# Arch_GPRS_v2_0.net
KiCad netlist of a schematic drawn in EAGLE
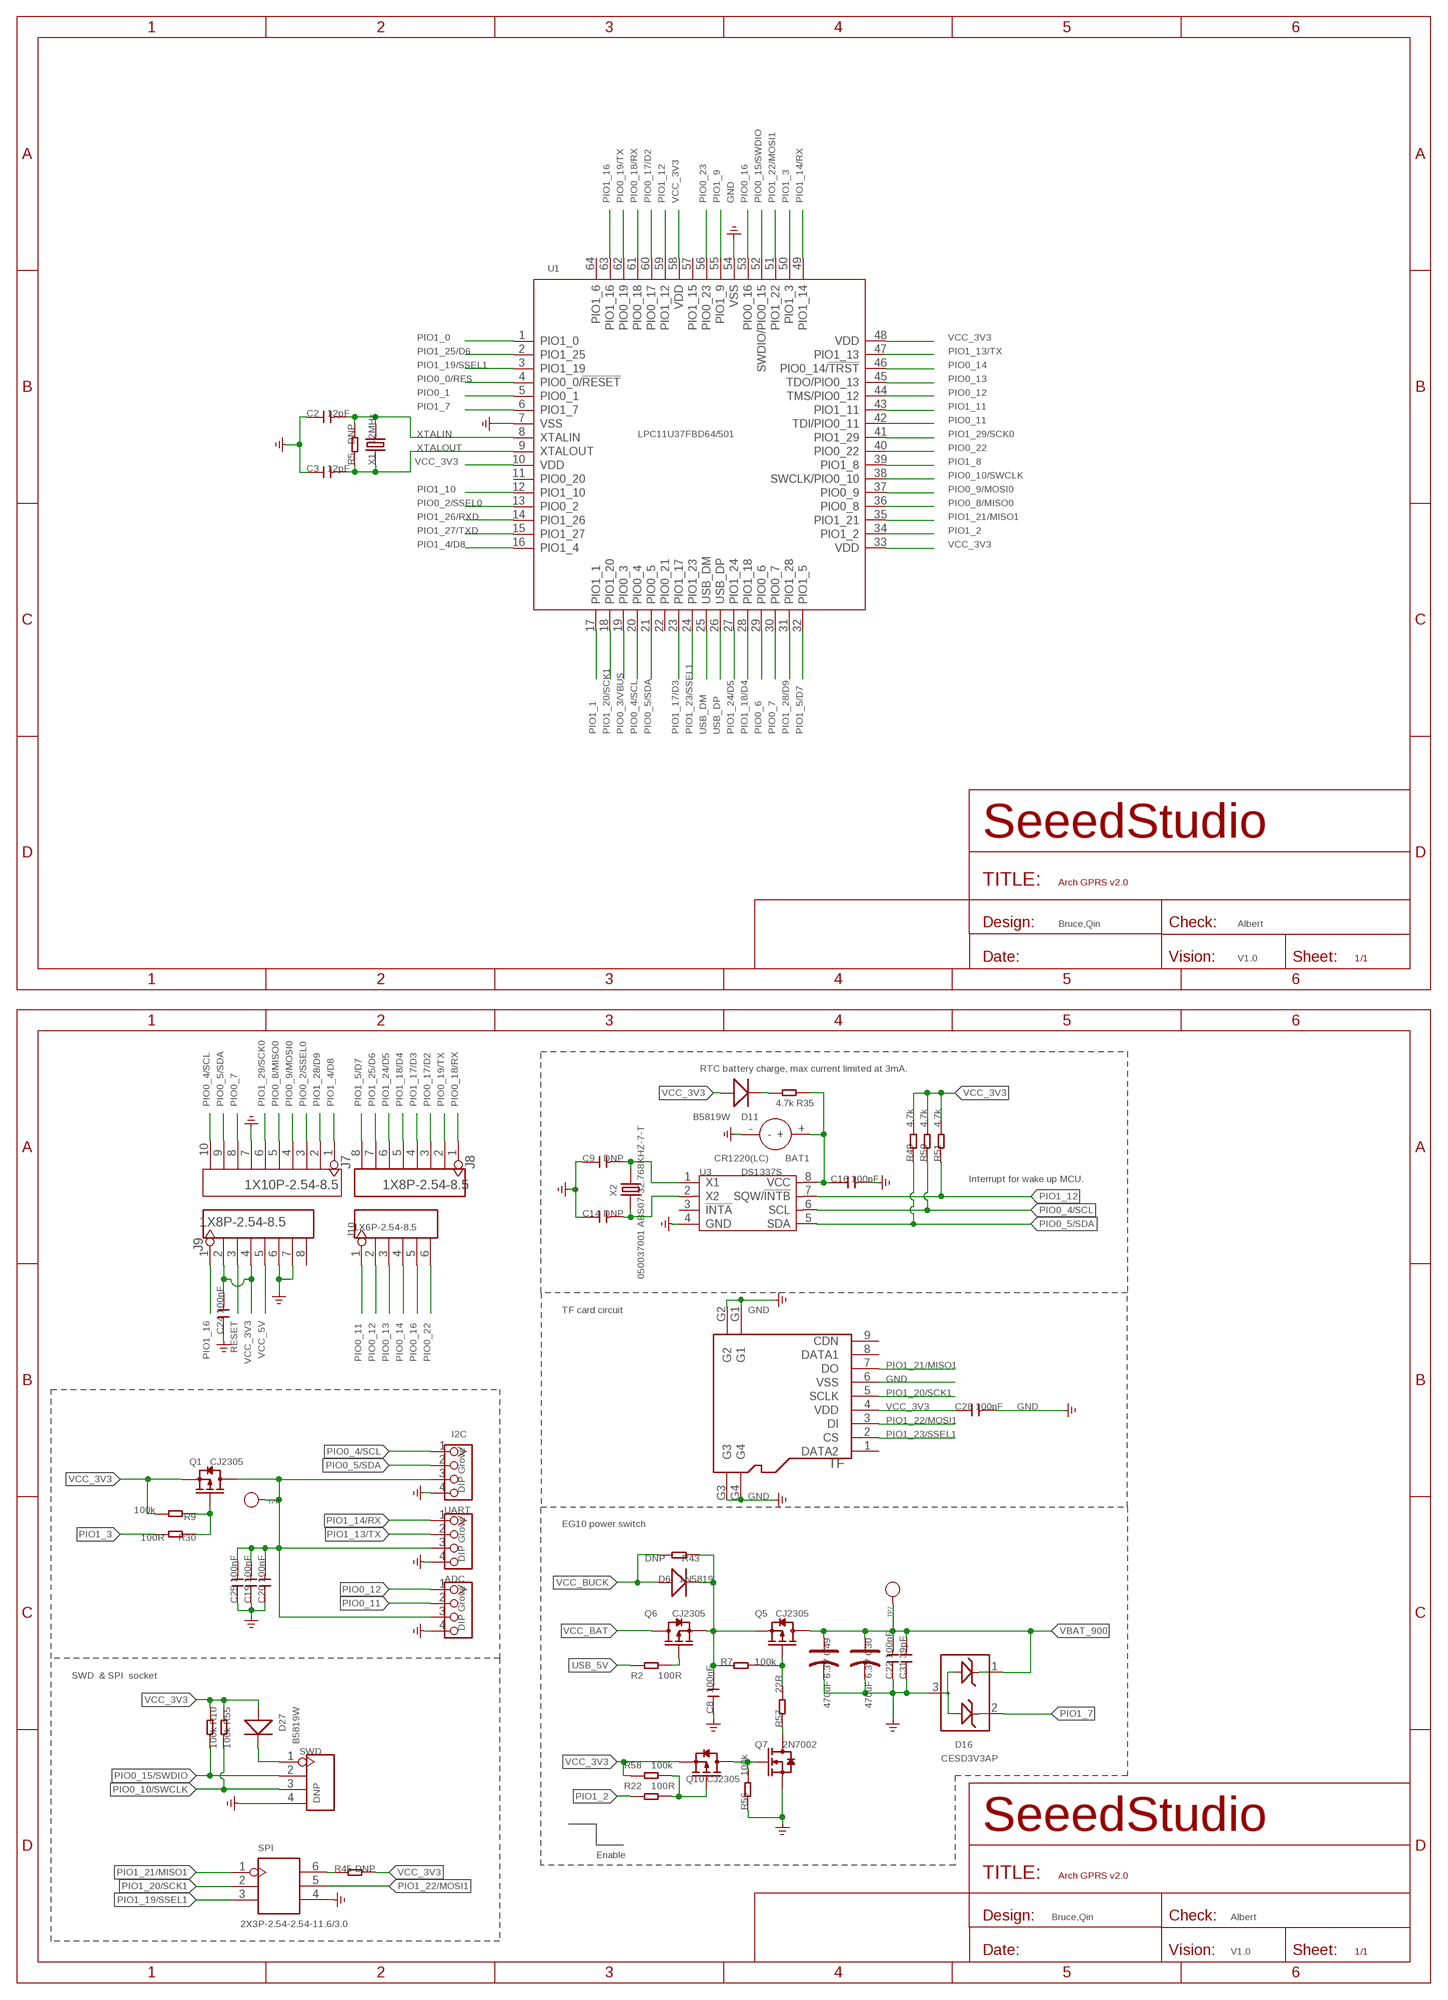
[diagram p0: schematic, sheet 1, part 1 of 2]
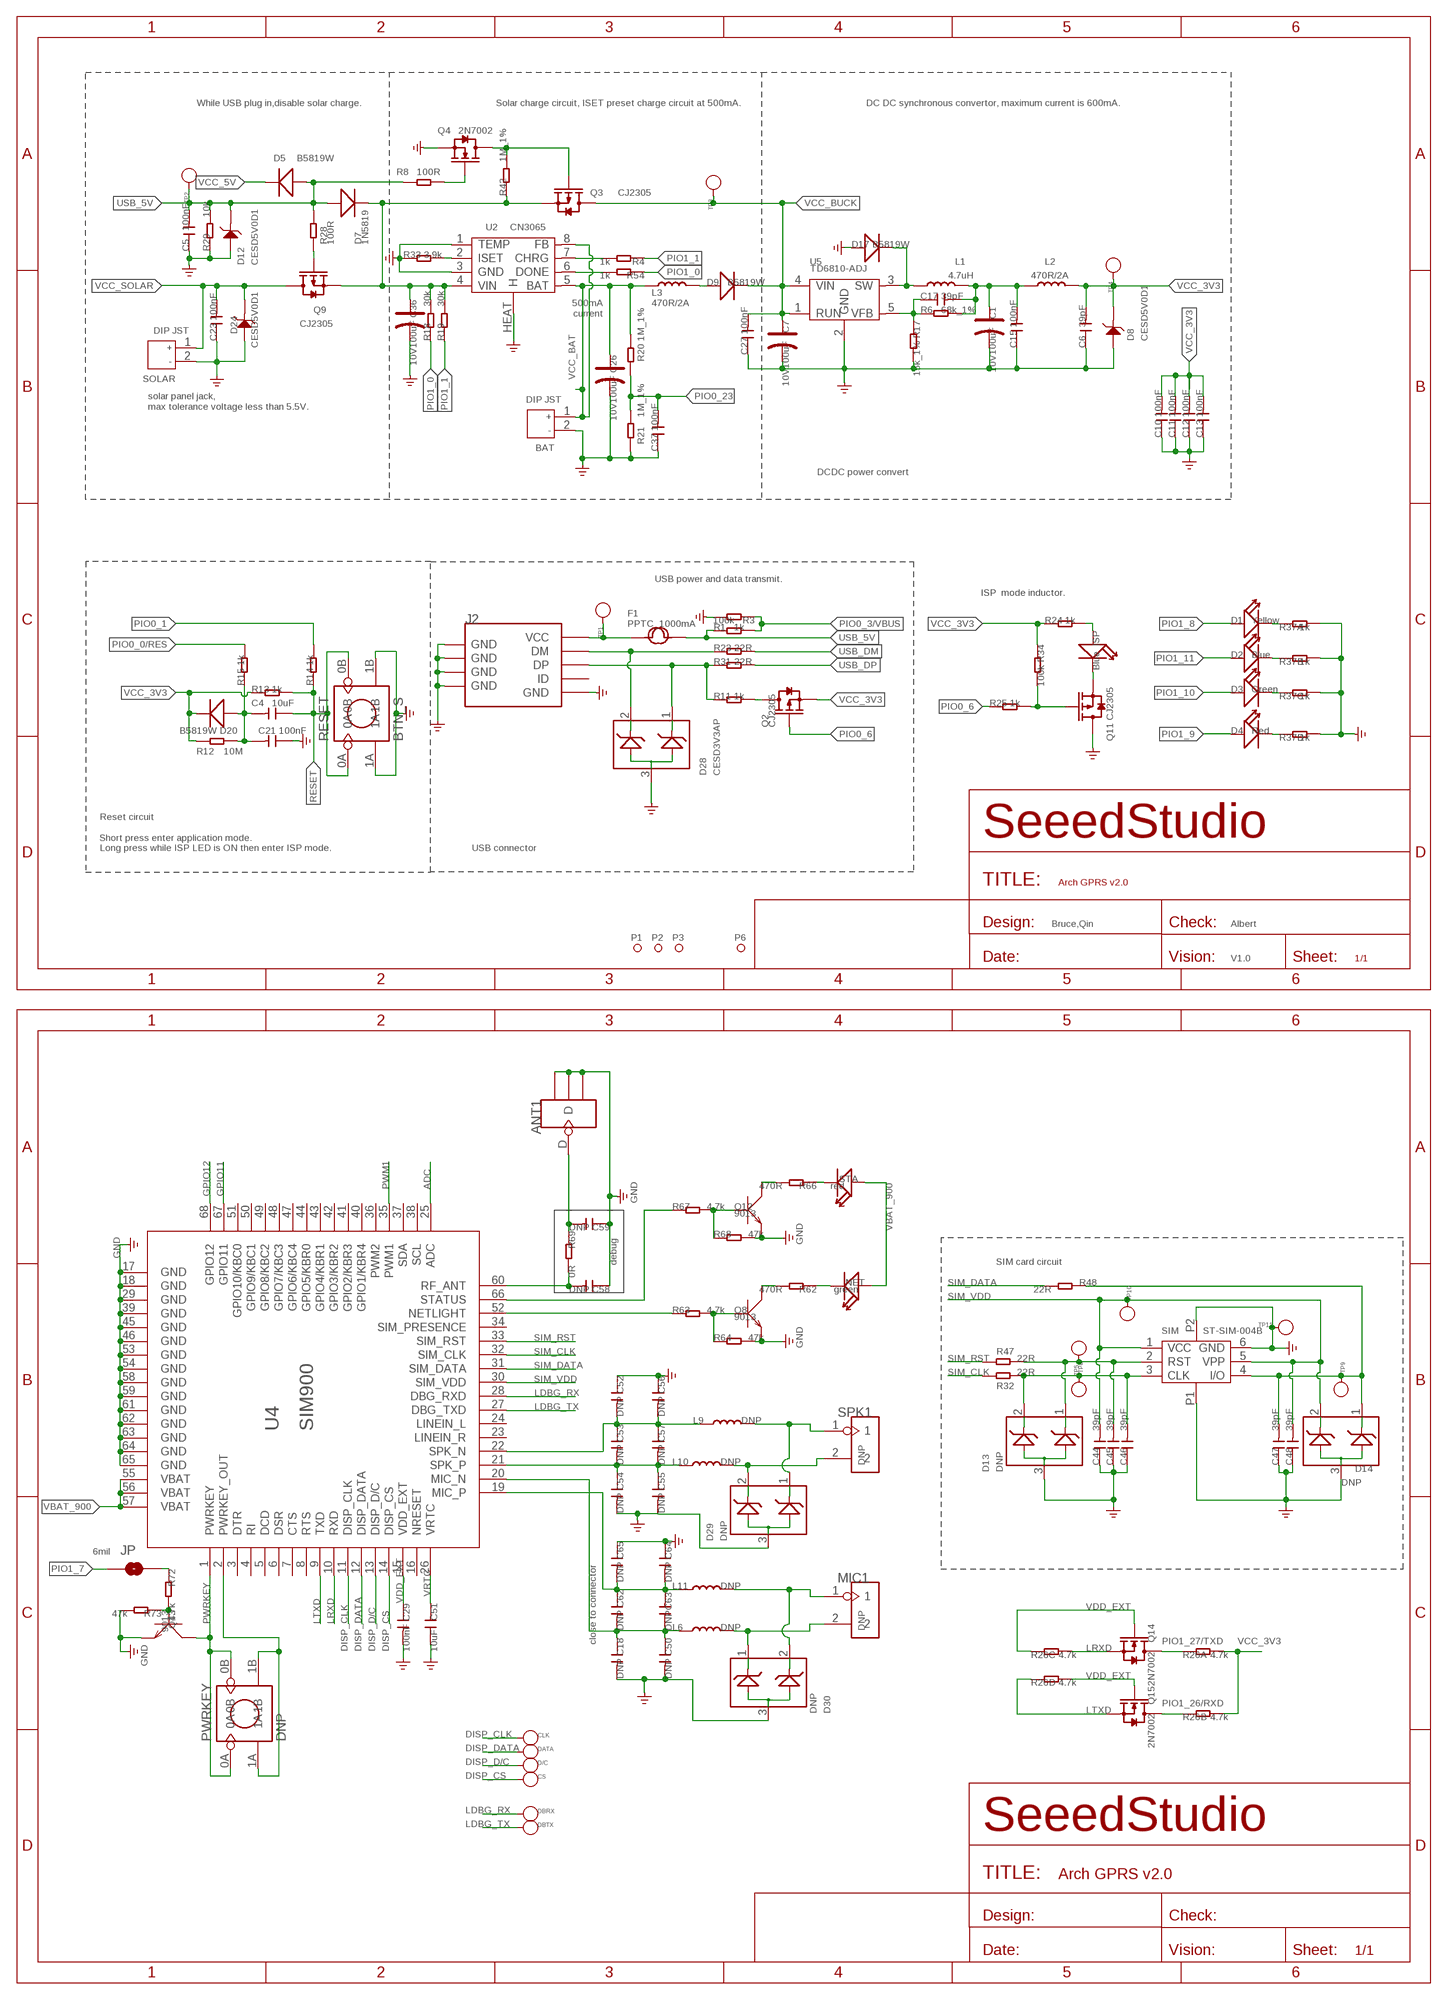
[diagram p1: schematic, sheet 1, part 2 of 2]

(export (version "E")
  (design (tool "Eeschema 10.0.6"))
  (components
    (comp (ref "ADC")
      (value "DIP Grove")
      (footprint "eagle-import:4P-2.0")
      (libsource (lib "eagle-import") (part "TWIG-4P-2.0-2.0"))
    )
    (comp (ref "ANT1")
      (value "ANTENNA-U-FL")
      (footprint "eagle-import:4P-U-FL")
      (libsource (lib "eagle-import") (part "ANTENNA-U-FL"))
    )
    (comp (ref "BAT")
      (value "DIP JST")
      (footprint "eagle-import:JST-2.0")
      (libsource (lib "eagle-import") (part "JACK-JST-2P-PW'2.0'"))
    )
    (comp (ref "BAT1")
      (value "CR1220(LC)")
      (footprint "eagle-import:2P-D12.55X2.22H")
      (libsource (lib "eagle-import") (part "BATTERY-3V"))
    )
    (comp (ref "C1")
      (value "10V100uF")
      (footprint "eagle-import:AVX-B")
      (libsource (lib "eagle-import") (part "CAP-AVX-B"))
    )
    (comp (ref "C2")
      (value "12pF")
      (footprint "eagle-import:C0603")
      (libsource (lib "eagle-import") (part "C-0603"))
    )
    (comp (ref "C3")
      (value "12pF")
      (footprint "eagle-import:C0603")
      (libsource (lib "eagle-import") (part "C-0603"))
    )
    (comp (ref "C4")
      (value "10uF")
      (footprint "eagle-import:C0805")
      (libsource (lib "eagle-import") (part "C-0805"))
    )
    (comp (ref "C5")
      (value "100nF")
      (footprint "eagle-import:C0603")
      (libsource (lib "eagle-import") (part "C-0603"))
    )
    (comp (ref "C6")
      (value "39pF")
      (footprint "eagle-import:C0603")
      (libsource (lib "eagle-import") (part "C-0603"))
    )
    (comp (ref "C7")
      (value "10V100uF")
      (footprint "eagle-import:AVX-B")
      (libsource (lib "eagle-import") (part "CAP-AVX-B"))
    )
    (comp (ref "C8")
      (value "100nF")
      (footprint "eagle-import:C0603")
      (libsource (lib "eagle-import") (part "C-0603"))
    )
    (comp (ref "C9")
      (value "DNP")
      (footprint "eagle-import:C0603")
      (libsource (lib "eagle-import") (part "C-0603"))
    )
    (comp (ref "C10")
      (value "100nF")
      (footprint "eagle-import:C0603")
      (libsource (lib "eagle-import") (part "C-0603"))
    )
    (comp (ref "C11")
      (value "100nF")
      (footprint "eagle-import:C0603")
      (libsource (lib "eagle-import") (part "C-0603"))
    )
    (comp (ref "C12")
      (value "100nF")
      (footprint "eagle-import:C0603")
      (libsource (lib "eagle-import") (part "C-0603"))
    )
    (comp (ref "C13")
      (value "100nF")
      (footprint "eagle-import:C0603")
      (libsource (lib "eagle-import") (part "C-0603"))
    )
    (comp (ref "C14")
      (value "DNP")
      (footprint "eagle-import:C0603")
      (libsource (lib "eagle-import") (part "C-0603"))
    )
    (comp (ref "C15")
      (value "100nF")
      (footprint "eagle-import:C0603")
      (libsource (lib "eagle-import") (part "C-0603"))
    )
    (comp (ref "C16")
      (value "100nF")
      (footprint "eagle-import:C0603")
      (libsource (lib "eagle-import") (part "C-0603"))
    )
    (comp (ref "C17")
      (value "39pF")
      (footprint "eagle-import:C0603")
      (libsource (lib "eagle-import") (part "C-0603"))
    )
    (comp (ref "C18")
      (value "DNP")
      (footprint "eagle-import:C0603")
      (libsource (lib "eagle-import") (part "C-0603"))
    )
    (comp (ref "C19")
      (value "100nF")
      (footprint "eagle-import:C0603")
      (libsource (lib "eagle-import") (part "C-0603"))
    )
    (comp (ref "C20")
      (value "100nF")
      (footprint "eagle-import:C0603")
      (libsource (lib "eagle-import") (part "C-0603"))
    )
    (comp (ref "C21")
      (value "100nF")
      (footprint "eagle-import:C0603")
      (libsource (lib "eagle-import") (part "C-0603"))
    )
    (comp (ref "C22")
      (value "100nF")
      (footprint "eagle-import:C0603")
      (libsource (lib "eagle-import") (part "C-0603"))
    )
    (comp (ref "C23")
      (value "100nF")
      (footprint "eagle-import:C0603")
      (libsource (lib "eagle-import") (part "C-0603"))
    )
    (comp (ref "C24")
      (value "100nF")
      (footprint "eagle-import:C0603")
      (libsource (lib "eagle-import") (part "C-0603"))
    )
    (comp (ref "C25")
      (value "100nF")
      (footprint "eagle-import:C0603")
      (libsource (lib "eagle-import") (part "C-0603"))
    )
    (comp (ref "C26")
      (value "10V100uF")
      (footprint "eagle-import:AVX-B")
      (libsource (lib "eagle-import") (part "CAP-AVX-B"))
    )
    (comp (ref "C27")
      (value "100nF")
      (footprint "eagle-import:C0603")
      (libsource (lib "eagle-import") (part "C-0603"))
    )
    (comp (ref "C28")
      (value "100nF")
      (footprint "eagle-import:C0603")
      (libsource (lib "eagle-import") (part "C-0603"))
    )
    (comp (ref "C29")
      (value "100nF")
      (footprint "eagle-import:C0603")
      (libsource (lib "eagle-import") (part "C-0603"))
    )
    (comp (ref "C30")
      (value "470uF 6.3V")
      (footprint "eagle-import:AVX-D")
      (libsource (lib "eagle-import") (part "CAP-AVX-D"))
    )
    (comp (ref "C31")
      (value "39pF")
      (footprint "eagle-import:C0603")
      (libsource (lib "eagle-import") (part "C-0603"))
    )
    (comp (ref "C36")
      (value "10V100uF")
      (footprint "eagle-import:AVX-B")
      (libsource (lib "eagle-import") (part "CAP-AVX-B"))
    )
    (comp (ref "C37")
      (value "100nF")
      (footprint "eagle-import:C0603")
      (libsource (lib "eagle-import") (part "C-0603"))
    )
    (comp (ref "C44")
      (value "39pF")
      (footprint "eagle-import:C0603")
      (libsource (lib "eagle-import") (part "C-0603"))
    )
    (comp (ref "C45")
      (value "39pF")
      (footprint "eagle-import:C0603")
      (libsource (lib "eagle-import") (part "C-0603"))
    )
    (comp (ref "C46")
      (value "39pF")
      (footprint "eagle-import:C0603")
      (libsource (lib "eagle-import") (part "C-0603"))
    )
    (comp (ref "C47")
      (value "39pF")
      (footprint "eagle-import:C0603")
      (libsource (lib "eagle-import") (part "C-0603"))
    )
    (comp (ref "C48")
      (value "39pF")
      (footprint "eagle-import:C0603")
      (libsource (lib "eagle-import") (part "C-0603"))
    )
    (comp (ref "C49")
      (value "470uF 6.3V")
      (footprint "eagle-import:AVX-D")
      (libsource (lib "eagle-import") (part "CAP-AVX-D"))
    )
    (comp (ref "C50")
      (value "DNP")
      (footprint "eagle-import:C0603")
      (libsource (lib "eagle-import") (part "C-0603"))
    )
    (comp (ref "C51")
      (value "10uF")
      (footprint "eagle-import:C0805")
      (libsource (lib "eagle-import") (part "C-0805"))
    )
    (comp (ref "C52")
      (value "DNP")
      (footprint "eagle-import:C0603")
      (libsource (lib "eagle-import") (part "C-0603"))
    )
    (comp (ref "C53")
      (value "DNP")
      (footprint "eagle-import:C0603")
      (libsource (lib "eagle-import") (part "C-0603"))
    )
    (comp (ref "C54")
      (value "DNP")
      (footprint "eagle-import:C0603")
      (libsource (lib "eagle-import") (part "C-0603"))
    )
    (comp (ref "C55")
      (value "DNP")
      (footprint "eagle-import:C0603")
      (libsource (lib "eagle-import") (part "C-0603"))
    )
    (comp (ref "C56")
      (value "DNP")
      (footprint "eagle-import:C0603")
      (libsource (lib "eagle-import") (part "C-0603"))
    )
    (comp (ref "C57")
      (value "DNP")
      (footprint "eagle-import:C0603")
      (libsource (lib "eagle-import") (part "C-0603"))
    )
    (comp (ref "C58")
      (value "DNP")
      (footprint "eagle-import:C0603")
      (libsource (lib "eagle-import") (part "C-0603"))
    )
    (comp (ref "C59")
      (value "DNP")
      (footprint "eagle-import:C0603")
      (libsource (lib "eagle-import") (part "C-0603"))
    )
    (comp (ref "C62")
      (value "DNP")
      (footprint "eagle-import:C0603")
      (libsource (lib "eagle-import") (part "C-0603"))
    )
    (comp (ref "C63")
      (value "DNP")
      (footprint "eagle-import:C0603")
      (libsource (lib "eagle-import") (part "C-0603"))
    )
    (comp (ref "C64")
      (value "DNP")
      (footprint "eagle-import:C0603")
      (libsource (lib "eagle-import") (part "C-0603"))
    )
    (comp (ref "C65")
      (value "DNP")
      (footprint "eagle-import:C0603")
      (libsource (lib "eagle-import") (part "C-0603"))
    )
    (comp (ref "CLK")
      (value "PAD-TEST-POINT-CIRCLE'4545'")
      (footprint "eagle-import:TP_4545")
      (fields (field (name "PARTNO") "DNP"))
      (libsource (lib "eagle-import") (part "PAD-TEST-POINT-CIRCLE'4545'"))
    )
    (comp (ref "CS")
      (value "PAD-TEST-POINT-CIRCLE'4545'")
      (footprint "eagle-import:TP_4545")
      (fields (field (name "PARTNO") "DNP"))
      (libsource (lib "eagle-import") (part "PAD-TEST-POINT-CIRCLE'4545'"))
    )
    (comp (ref "D/C")
      (value "PAD-TEST-POINT-CIRCLE'4545'")
      (footprint "eagle-import:TP_4545")
      (fields (field (name "PARTNO") "DNP"))
      (libsource (lib "eagle-import") (part "PAD-TEST-POINT-CIRCLE'4545'"))
    )
    (comp (ref "D1")
      (value "Yellow")
      (footprint "eagle-import:LED-0603")
      (libsource (lib "eagle-import") (part "LED'0603'"))
    )
    (comp (ref "D2")
      (value "Blue")
      (footprint "eagle-import:LED-0603")
      (libsource (lib "eagle-import") (part "LED'0603'"))
    )
    (comp (ref "D3")
      (value "Green")
      (footprint "eagle-import:LED-0603")
      (libsource (lib "eagle-import") (part "LED'0603'"))
    )
    (comp (ref "D4")
      (value "Red")
      (footprint "eagle-import:LED-0603")
      (libsource (lib "eagle-import") (part "LED'0603'"))
    )
    (comp (ref "D5")
      (value "B5819W")
      (footprint "eagle-import:SOD123")
      (libsource (lib "eagle-import") (part "D'1206'"))
    )
    (comp (ref "D6")
      (value "1N5819")
      (footprint "eagle-import:SMA")
      (libsource (lib "eagle-import") (part "D'B130L-13-F'"))
    )
    (comp (ref "D7")
      (value "1N5819")
      (footprint "eagle-import:SMA")
      (libsource (lib "eagle-import") (part "D'B130L-13-F'"))
    )
    (comp (ref "D8")
      (value "CESD5V0D1")
      (footprint "eagle-import:SOD123-2.7X1.6")
      (libsource (lib "eagle-import") (part "D-ESD-2P'CESD5V0D1'"))
    )
    (comp (ref "D9")
      (value "B5819W")
      (footprint "eagle-import:SOD123")
      (libsource (lib "eagle-import") (part "D'1206'"))
    )
    (comp (ref "D11")
      (value "B5819W")
      (footprint "eagle-import:SOD123")
      (libsource (lib "eagle-import") (part "D'1206'"))
    )
    (comp (ref "D12")
      (value "CESD5V0D1")
      (footprint "eagle-import:SOD123-2.7X1.6")
      (libsource (lib "eagle-import") (part "D-ESD-2P'CESD5V0D1'"))
    )
    (comp (ref "D13")
      (value "DNP")
      (footprint "eagle-import:SOT23")
      (libsource (lib "eagle-import") (part "D-ESD-3P"))
    )
    (comp (ref "D14")
      (value "DNP")
      (footprint "eagle-import:SOT23")
      (libsource (lib "eagle-import") (part "D-ESD-3P"))
    )
    (comp (ref "D16")
      (value "CESD3V3AP")
      (footprint "eagle-import:SOT23")
      (libsource (lib "eagle-import") (part "D-ESD-3P"))
    )
    (comp (ref "D17")
      (value "B5819W")
      (footprint "eagle-import:SOD123")
      (libsource (lib "eagle-import") (part "D'1206'"))
    )
    (comp (ref "D20")
      (value "B5819W")
      (footprint "eagle-import:SOD123")
      (libsource (lib "eagle-import") (part "D'1206'"))
    )
    (comp (ref "D24")
      (value "CESD5V0D1")
      (footprint "eagle-import:SOD123-2.7X1.6")
      (libsource (lib "eagle-import") (part "D-ESD-2P'CESD5V0D1'"))
    )
    (comp (ref "D27")
      (value "B5819W")
      (footprint "eagle-import:SOD123")
      (libsource (lib "eagle-import") (part "D'1206'"))
    )
    (comp (ref "D28")
      (value "CESD3V3AP")
      (footprint "eagle-import:SOT23")
      (libsource (lib "eagle-import") (part "D-ESD-3P"))
    )
    (comp (ref "D29")
      (value "DNP")
      (footprint "eagle-import:SOT23")
      (libsource (lib "eagle-import") (part "D-ESD-3P"))
    )
    (comp (ref "D30")
      (value "DNP")
      (footprint "eagle-import:SOT23")
      (libsource (lib "eagle-import") (part "D-ESD-3P"))
    )
    (comp (ref "DATA")
      (value "PAD-TEST-POINT-CIRCLE'4545'")
      (footprint "eagle-import:TP_4545")
      (fields (field (name "PARTNO") "DNP"))
      (libsource (lib "eagle-import") (part "PAD-TEST-POINT-CIRCLE'4545'"))
    )
    (comp (ref "DBRX")
      (value "DBURX")
      (footprint "eagle-import:TP_4545")
      (fields (field (name "PARTNO") "DNP"))
      (libsource (lib "eagle-import") (part "PAD-TEST-POINT-CIRCLE'4545'"))
    )
    (comp (ref "DBTX")
      (value "PAD-TEST-POINT-CIRCLE'4545'")
      (footprint "eagle-import:TP_4545")
      (fields (field (name "PARTNO") "DNP"))
      (libsource (lib "eagle-import") (part "PAD-TEST-POINT-CIRCLE'4545'"))
    )
    (comp (ref "F1")
      (value "PPTC_1000mA")
      (footprint "eagle-import:F1206")
      (libsource (lib "eagle-import") (part "FUSE'1206'"))
    )
    (comp (ref "I2C")
      (value "DIP Grove")
      (footprint "eagle-import:4P-2.0")
      (libsource (lib "eagle-import") (part "TWIG-4P-2.0-2.0"))
    )
    (comp (ref "ISP")
      (value "Blue")
      (footprint "eagle-import:LED-0603")
      (libsource (lib "eagle-import") (part "LED'0603'"))
    )
    (comp (ref "J2")
      (value "USB-MINIUSB-5P-MICRO")
      (footprint "eagle-import:MICRO-USB")
      (libsource (lib "eagle-import") (part "USB-MINIUSB-5P-MICRO"))
    )
    (comp (ref "J7")
      (value "1X10P-2.54-8.5")
      (footprint "eagle-import:10P-2.54")
      (libsource (lib "eagle-import") (part "HEADER-10P-2.54"))
    )
    (comp (ref "J8")
      (value "1X8P-2.54-8.5")
      (footprint "eagle-import:8P-2.54")
      (libsource (lib "eagle-import") (part "HEADER-8P-2.54"))
    )
    (comp (ref "J9")
      (value "1X8P-2.54-8.5")
      (footprint "eagle-import:8P-2.54")
      (libsource (lib "eagle-import") (part "HEADER-8P-2.54"))
    )
    (comp (ref "J10")
      (value "1X6P-2.54-8.5")
      (footprint "eagle-import:6P-2.54-65_35MIL")
      (libsource (lib "eagle-import") (part "HEADER-6P-65/35MIL"))
    )
    (comp (ref "JP")
      (value "PAD-SOLDERJUMPERNC")
      (footprint "eagle-import:2P-SMD-3.3X2")
      (libsource (lib "eagle-import") (part "PAD-SOLDERJUMPERNC"))
    )
    (comp (ref "L1")
      (value "4.7uH")
      (footprint "eagle-import:L0420")
      (libsource (lib "eagle-import") (part "LSPD3D16-4R7M"))
    )
    (comp (ref "L2")
      (value "470R/2A")
      (footprint "eagle-import:L0805")
      (libsource (lib "eagle-import") (part "L'0805'"))
    )
    (comp (ref "L3")
      (value "470R/2A")
      (footprint "eagle-import:L0805")
      (libsource (lib "eagle-import") (part "L'0805'"))
    )
    (comp (ref "L6")
      (value "DNP")
      (footprint "eagle-import:L0603")
      (libsource (lib "eagle-import") (part "L'0603'"))
    )
    (comp (ref "L9")
      (value "DNP")
      (footprint "eagle-import:L0603")
      (libsource (lib "eagle-import") (part "L'0603'"))
    )
    (comp (ref "L10")
      (value "DNP")
      (footprint "eagle-import:L0603")
      (libsource (lib "eagle-import") (part "L'0603'"))
    )
    (comp (ref "L11")
      (value "DNP")
      (footprint "eagle-import:L0603")
      (libsource (lib "eagle-import") (part "L'0603'"))
    )
    (comp (ref "MIC1")
      (value "DNP")
      (footprint "eagle-import:2P-2.0")
      (libsource (lib "eagle-import") (part "HEADER-2P-2.0"))
    )
    (comp (ref "NET")
      (value "green")
      (footprint "eagle-import:LED-0603")
      (libsource (lib "eagle-import") (part "LED'0603'"))
    )
    (comp (ref "P1")
      (value "PAD-MARK")
      (footprint "eagle-import:ROUND-MARK-1.0")
      (fields (field (name "PARTNO") "DNP"))
      (libsource (lib "eagle-import") (part "PAD-MARK"))
    )
    (comp (ref "P2")
      (value "PAD-MARK")
      (footprint "eagle-import:ROUND-MARK-1.0")
      (fields (field (name "PARTNO") "DNP"))
      (libsource (lib "eagle-import") (part "PAD-MARK"))
    )
    (comp (ref "P3")
      (value "PAD-MARK")
      (footprint "eagle-import:ROUND-MARK-1.0")
      (fields (field (name "PARTNO") "DNP"))
      (libsource (lib "eagle-import") (part "PAD-MARK"))
    )
    (comp (ref "P6")
      (value "PAD-MARK")
      (footprint "eagle-import:ROUND-MARK-1.0")
      (fields (field (name "PARTNO") "DNP"))
      (libsource (lib "eagle-import") (part "PAD-MARK"))
    )
    (comp (ref "PWRKEY")
      (value "DNP")
      (footprint "eagle-import:BTN_S")
      (libsource (lib "eagle-import") (part "BTN_S"))
    )
    (comp (ref "Q1")
      (value "CJ2305")
      (footprint "eagle-import:SOT23")
      (libsource (lib "eagle-import") (part "MOSFET-P'SI2323CDS/SI2305DS{lt}BR{gt}'"))
    )
    (comp (ref "Q2")
      (value "CJ2305")
      (footprint "eagle-import:SOT23")
      (libsource (lib "eagle-import") (part "MOSFET-P'SI2323CDS/SI2305DS{lt}BR{gt}'"))
    )
    (comp (ref "Q3")
      (value "CJ2305")
      (footprint "eagle-import:SOT23")
      (libsource (lib "eagle-import") (part "MOSFET-P'SI2323CDS/SI2305DS{lt}BR{gt}'"))
    )
    (comp (ref "Q4")
      (value "2N7002")
      (footprint "eagle-import:SOT23")
      (libsource (lib "eagle-import") (part "MOSFET-N'SOT23'"))
    )
    (comp (ref "Q5")
      (value "CJ2305")
      (footprint "eagle-import:SOT23")
      (libsource (lib "eagle-import") (part "MOSFET-P'SI2323CDS/SI2305DS{lt}BR{gt}'"))
    )
    (comp (ref "Q6")
      (value "CJ2305")
      (footprint "eagle-import:SOT23")
      (libsource (lib "eagle-import") (part "MOSFET-P'SI2323CDS/SI2305DS{lt}BR{gt}'"))
    )
    (comp (ref "Q7")
      (value "2N7002")
      (footprint "eagle-import:SOT23")
      (libsource (lib "eagle-import") (part "MOSFET-N'SOT23'"))
    )
    (comp (ref "Q8")
      (value "9013")
      (footprint "eagle-import:SOT23")
      (libsource (lib "eagle-import") (part "TRANSISTOR-NPN-SOT23"))
    )
    (comp (ref "Q9")
      (value "CJ2305")
      (footprint "eagle-import:SOT23")
      (libsource (lib "eagle-import") (part "MOSFET-P'SI2323CDS/SI2305DS{lt}BR{gt}'"))
    )
    (comp (ref "Q10")
      (value "CJ2305")
      (footprint "eagle-import:SOT23")
      (libsource (lib "eagle-import") (part "MOSFET-P'SI2323CDS/SI2305DS{lt}BR{gt}'"))
    )
    (comp (ref "Q11")
      (value "CJ2305")
      (footprint "eagle-import:SOT23")
      (libsource (lib "eagle-import") (part "MOSFET-P'SI2323CDS/SI2305DS{lt}BR{gt}'"))
    )
    (comp (ref "Q12")
      (value "9013")
      (footprint "eagle-import:SOT23")
      (libsource (lib "eagle-import") (part "TRANSISTOR-NPN-SOT23"))
    )
    (comp (ref "Q13")
      (value "9013")
      (footprint "eagle-import:SOT23")
      (libsource (lib "eagle-import") (part "TRANSISTOR-NPN-SOT23"))
    )
    (comp (ref "Q14")
      (value "2N7002")
      (footprint "eagle-import:SOT23")
      (libsource (lib "eagle-import") (part "MOSFET-N'SOT23'"))
    )
    (comp (ref "Q15")
      (value "2N7002")
      (footprint "eagle-import:SOT23")
      (libsource (lib "eagle-import") (part "MOSFET-N'SOT23'"))
    )
    (comp (ref "R1")
      (value "1k")
      (footprint "eagle-import:R0603")
      (libsource (lib "eagle-import") (part "R-0603"))
    )
    (comp (ref "R2")
      (value "100R")
      (footprint "eagle-import:R0603")
      (libsource (lib "eagle-import") (part "R-0603"))
    )
    (comp (ref "R3")
      (value "100k")
      (footprint "eagle-import:R0603")
      (libsource (lib "eagle-import") (part "R-0603"))
    )
    (comp (ref "R4")
      (value "1k")
      (footprint "eagle-import:R0603")
      (libsource (lib "eagle-import") (part "R-0603"))
    )
    (comp (ref "R5")
      (value "DNP")
      (footprint "eagle-import:R0603")
      (libsource (lib "eagle-import") (part "R-0603"))
    )
    (comp (ref "R6")
      (value "68k_1%")
      (footprint "eagle-import:R0603")
      (libsource (lib "eagle-import") (part "R-0603"))
    )
    (comp (ref "R7")
      (value "100k")
      (footprint "eagle-import:R0603")
      (libsource (lib "eagle-import") (part "R-0603"))
    )
    (comp (ref "R8")
      (value "100R")
      (footprint "eagle-import:R0603")
      (libsource (lib "eagle-import") (part "R-0603"))
    )
    (comp (ref "R9")
      (value "100k")
      (footprint "eagle-import:R0603")
      (libsource (lib "eagle-import") (part "R-0603"))
    )
    (comp (ref "R10")
      (value "100k")
      (footprint "eagle-import:R0603")
      (libsource (lib "eagle-import") (part "R-0603"))
    )
    (comp (ref "R11")
      (value "1k")
      (footprint "eagle-import:R0603")
      (libsource (lib "eagle-import") (part "R-0603"))
    )
    (comp (ref "R12")
      (value "10M")
      (footprint "eagle-import:R0603")
      (libsource (lib "eagle-import") (part "R-0603"))
    )
    (comp (ref "R13")
      (value "1k")
      (footprint "eagle-import:R0603")
      (libsource (lib "eagle-import") (part "R-0603"))
    )
    (comp (ref "R14")
      (value "1k")
      (footprint "eagle-import:R0603")
      (libsource (lib "eagle-import") (part "R-0603"))
    )
    (comp (ref "R15")
      (value "1k")
      (footprint "eagle-import:R0603")
      (libsource (lib "eagle-import") (part "R-0603"))
    )
    (comp (ref "R17")
      (value "15k_1%")
      (footprint "eagle-import:R0603")
      (libsource (lib "eagle-import") (part "R-0603"))
    )
    (comp (ref "R18")
      (value "30k")
      (footprint "eagle-import:R0603")
      (libsource (lib "eagle-import") (part "R-0603"))
    )
    (comp (ref "R19")
      (value "30k")
      (footprint "eagle-import:R0603")
      (libsource (lib "eagle-import") (part "R-0603"))
    )
    (comp (ref "R20")
      (value "1M_1%")
      (footprint "eagle-import:R0603")
      (libsource (lib "eagle-import") (part "R-0603"))
    )
    (comp (ref "R21")
      (value "1M_1%")
      (footprint "eagle-import:R0603")
      (libsource (lib "eagle-import") (part "R-0603"))
    )
    (comp (ref "R22")
      (value "100R")
      (footprint "eagle-import:R0603")
      (libsource (lib "eagle-import") (part "R-0603"))
    )
    (comp (ref "R23")
      (value "22R")
      (footprint "eagle-import:R0603")
      (libsource (lib "eagle-import") (part "R-0603"))
    )
    (comp (ref "R24")
      (value "1k")
      (footprint "eagle-import:R0603")
      (libsource (lib "eagle-import") (part "R-0603"))
    )
    (comp (ref "R25")
      (value "1k")
      (footprint "eagle-import:R0603")
      (libsource (lib "eagle-import") (part "R-0603"))
    )
    (comp (ref "R26")
      (value "4.7k")
      (footprint "eagle-import:1206-8-3.3X2.4")
      (libsource (lib "eagle-import") (part "R-4R-1206"))
    )
    (comp (ref "R28")
      (value "100R")
      (footprint "eagle-import:R0603")
      (libsource (lib "eagle-import") (part "R-0603"))
    )
    (comp (ref "R29")
      (value "10k")
      (footprint "eagle-import:R0603")
      (libsource (lib "eagle-import") (part "R-0603"))
    )
    (comp (ref "R30")
      (value "100R")
      (footprint "eagle-import:R0603")
      (libsource (lib "eagle-import") (part "R-0603"))
    )
    (comp (ref "R31")
      (value "22R")
      (footprint "eagle-import:R0603")
      (libsource (lib "eagle-import") (part "R-0603"))
    )
    (comp (ref "R32")
      (value "22R")
      (footprint "eagle-import:R0603")
      (libsource (lib "eagle-import") (part "R-0603"))
    )
    (comp (ref "R33")
      (value "3.9k")
      (footprint "eagle-import:R0603")
      (libsource (lib "eagle-import") (part "R-0603"))
    )
    (comp (ref "R34")
      (value "100k")
      (footprint "eagle-import:R0603")
      (libsource (lib "eagle-import") (part "R-0603"))
    )
    (comp (ref "R35")
      (value "4.7k")
      (footprint "eagle-import:R0603")
      (libsource (lib "eagle-import") (part "R-0603"))
    )
    (comp (ref "R37")
      (value "1k")
      (footprint "eagle-import:1206-8-3.3X2.4")
      (libsource (lib "eagle-import") (part "R-4R-1206"))
    )
    (comp (ref "R42")
      (value "1M_1%")
      (footprint "eagle-import:R0603")
      (libsource (lib "eagle-import") (part "R-0603"))
    )
    (comp (ref "R43")
      (value "DNP")
      (footprint "eagle-import:R0603")
      (libsource (lib "eagle-import") (part "R-0603"))
    )
    (comp (ref "R45")
      (value "DNP")
      (footprint "eagle-import:R0603")
      (libsource (lib "eagle-import") (part "R-0603"))
    )
    (comp (ref "R47")
      (value "22R")
      (footprint "eagle-import:R0603")
      (libsource (lib "eagle-import") (part "R-0603"))
    )
    (comp (ref "R48")
      (value "22R")
      (footprint "eagle-import:R0603")
      (libsource (lib "eagle-import") (part "R-0603"))
    )
    (comp (ref "R49")
      (value "4.7k")
      (footprint "eagle-import:R0603")
      (libsource (lib "eagle-import") (part "R-0603"))
    )
    (comp (ref "R50")
      (value "4.7k")
      (footprint "eagle-import:R0603")
      (libsource (lib "eagle-import") (part "R-0603"))
    )
    (comp (ref "R51")
      (value "4.7k")
      (footprint "eagle-import:R0603")
      (libsource (lib "eagle-import") (part "R-0603"))
    )
    (comp (ref "R54")
      (value "1k")
      (footprint "eagle-import:R0603")
      (libsource (lib "eagle-import") (part "R-0603"))
    )
    (comp (ref "R55")
      (value "100k")
      (footprint "eagle-import:R0603")
      (libsource (lib "eagle-import") (part "R-0603"))
    )
    (comp (ref "R56")
      (value "100k")
      (footprint "eagle-import:R0603")
      (libsource (lib "eagle-import") (part "R-0603"))
    )
    (comp (ref "R57")
      (value "22R")
      (footprint "eagle-import:R0603")
      (libsource (lib "eagle-import") (part "R-0603"))
    )
    (comp (ref "R58")
      (value "100k")
      (footprint "eagle-import:R0603")
      (libsource (lib "eagle-import") (part "R-0603"))
    )
    (comp (ref "R62")
      (value "470R")
      (footprint "eagle-import:R0603")
      (libsource (lib "eagle-import") (part "R-0603"))
    )
    (comp (ref "R63")
      (value "4.7k")
      (footprint "eagle-import:R0603")
      (libsource (lib "eagle-import") (part "R-0603"))
    )
    (comp (ref "R64")
      (value "47k")
      (footprint "eagle-import:R0603")
      (libsource (lib "eagle-import") (part "R-0603"))
    )
    (comp (ref "R66")
      (value "470R")
      (footprint "eagle-import:R0603")
      (libsource (lib "eagle-import") (part "R-0603"))
    )
    (comp (ref "R67")
      (value "4.7k")
      (footprint "eagle-import:R0603")
      (libsource (lib "eagle-import") (part "R-0603"))
    )
    (comp (ref "R68")
      (value "47k")
      (footprint "eagle-import:R0603")
      (libsource (lib "eagle-import") (part "R-0603"))
    )
    (comp (ref "R69")
      (value "0R")
      (footprint "eagle-import:R0603")
      (libsource (lib "eagle-import") (part "R-0603"))
    )
    (comp (ref "R72")
      (value "4.7k")
      (footprint "eagle-import:R0603")
      (libsource (lib "eagle-import") (part "R-0603"))
    )
    (comp (ref "R73")
      (value "47k")
      (footprint "eagle-import:R0603")
      (libsource (lib "eagle-import") (part "R-0603"))
    )
    (comp (ref "RESET")
      (value "BTN_S")
      (footprint "eagle-import:BTN_S")
      (libsource (lib "eagle-import") (part "BTN_S"))
    )
    (comp (ref "SIM")
      (value "ST-SIM-004B")
      (footprint "eagle-import:6P-1.8")
      (libsource (lib "eagle-import") (part "SIM-CARD'ST-SIM-004B'"))
    )
    (comp (ref "SOLAR")
      (value "DIP JST")
      (footprint "eagle-import:JST-2.0")
      (libsource (lib "eagle-import") (part "JACK-JST-2P-PW'2.0'"))
    )
    (comp (ref "SPI")
      (value "2X3P-2.54-2.54-11.6/3.0")
      (footprint "eagle-import:2X3P-2.54")
      (libsource (lib "eagle-import") (part "HEADER-2X3P-2.54"))
    )
    (comp (ref "SPK1")
      (value "DNP")
      (footprint "eagle-import:2P-2.0")
      (libsource (lib "eagle-import") (part "HEADER-2P-2.0"))
    )
    (comp (ref "STA")
      (value "red")
      (footprint "eagle-import:LED-0603")
      (libsource (lib "eagle-import") (part "LED'0603'"))
    )
    (comp (ref "SWD")
      (value "DNP")
      (footprint "eagle-import:4P-65_35MIL")
      (libsource (lib "eagle-import") (part "HEADER-4P-65/35MIL"))
    )
    (comp (ref "TF")
      (value "HOLDER-MICROSD-9P'HOLDER'")
      (footprint "eagle-import:9P-SMD-W_-RING")
      (libsource (lib "eagle-import") (part "HOLDER-MICROSD-9P'HOLDER'"))
    )
    (comp (ref "TP1")
      (value "PAD-TEST-POINT'4545'")
      (footprint "eagle-import:TP_4545")
      (fields (field (name "PARTNO") "DNP"))
      (libsource (lib "eagle-import") (part "PAD-TEST-POINT'4545'"))
    )
    (comp (ref "TP2")
      (value "PAD-TEST-POINT'4545'")
      (footprint "eagle-import:TP_4545")
      (fields (field (name "PARTNO") "DNP"))
      (libsource (lib "eagle-import") (part "PAD-TEST-POINT'4545'"))
    )
    (comp (ref "TP3")
      (value "PAD-TEST-POINT'4545'")
      (footprint "eagle-import:TP_4545")
      (fields (field (name "PARTNO") "DNP"))
      (libsource (lib "eagle-import") (part "PAD-TEST-POINT'4545'"))
    )
    (comp (ref "TP4")
      (value "PAD-TEST-POINT'4545'")
      (footprint "eagle-import:TP_4545")
      (fields (field (name "PARTNO") "DNP"))
      (libsource (lib "eagle-import") (part "PAD-TEST-POINT'4545'"))
    )
    (comp (ref "TP5")
      (value "PAD-TEST-POINT'4545'")
      (footprint "eagle-import:TP_4545")
      (fields (field (name "PARTNO") "DNP"))
      (libsource (lib "eagle-import") (part "PAD-TEST-POINT'4545'"))
    )
    (comp (ref "TP6")
      (value "PAD-TEST-POINT'4545'")
      (footprint "eagle-import:TP_4545")
      (fields (field (name "PARTNO") "DNP"))
      (libsource (lib "eagle-import") (part "PAD-TEST-POINT'4545'"))
    )
    (comp (ref "TP7")
      (value "PAD-TEST-POINT'4545'")
      (footprint "eagle-import:TP_4545")
      (fields (field (name "PARTNO") "DNP"))
      (libsource (lib "eagle-import") (part "PAD-TEST-POINT'4545'"))
    )
    (comp (ref "TP8")
      (value "PAD-TEST-POINT'4545'")
      (footprint "eagle-import:TP_4545")
      (fields (field (name "PARTNO") "DNP"))
      (libsource (lib "eagle-import") (part "PAD-TEST-POINT'4545'"))
    )
    (comp (ref "TP9")
      (value "PAD-TEST-POINT'4545'")
      (footprint "eagle-import:TP_4545")
      (fields (field (name "PARTNO") "DNP"))
      (libsource (lib "eagle-import") (part "PAD-TEST-POINT'4545'"))
    )
    (comp (ref "TP10")
      (value "PAD-TEST-POINT'4545'")
      (footprint "eagle-import:TP_4545")
      (fields (field (name "PARTNO") "DNP"))
      (libsource (lib "eagle-import") (part "PAD-TEST-POINT'4545'"))
    )
    (comp (ref "TP11")
      (value "PAD-TEST-POINT'4545'")
      (footprint "eagle-import:TP_4545")
      (fields (field (name "PARTNO") "DNP"))
      (libsource (lib "eagle-import") (part "PAD-TEST-POINT'4545'"))
    )
    (comp (ref "U1")
      (value "LPC11U37FBD64/501")
      (footprint "eagle-import:LQFP64")
      (libsource (lib "eagle-import") (part "LPC11U37FBD64/501"))
    )
    (comp (ref "U2")
      (value "CN3065")
      (footprint "eagle-import:DFN8")
      (libsource (lib "eagle-import") (part "CN3065-DFN8"))
    )
    (comp (ref "U3")
      (value "DS1337S")
      (footprint "eagle-import:SOP8")
      (libsource (lib "eagle-import") (part "DS1337S"))
    )
    (comp (ref "U4")
      (value "SIM900")
      (footprint "eagle-import:SIM900")
      (libsource (lib "eagle-import") (part "SIM900"))
    )
    (comp (ref "U5")
      (value "TD6810-ADJ")
      (footprint "eagle-import:SOT23-5")
      (libsource (lib "eagle-import") (part "TD6810'TSOT23-5'"))
    )
    (comp (ref "UART")
      (value "DIP Grove")
      (footprint "eagle-import:4P-2.0")
      (libsource (lib "eagle-import") (part "TWIG-4P-2.0-2.0"))
    )
    (comp (ref "X1")
      (value "12MHz")
      (footprint "eagle-import:2P-SMD-5X3.2")
      (libsource (lib "eagle-import") (part "CRYSTAL'5032'"))
    )
    (comp (ref "X2")
      (value "050037001 ABS07-32.768KHZ-7-T")
      (footprint "eagle-import:2P-SMD-3.2X1.5")
      (libsource (lib "eagle-import") (part "CRYSTAL-3215"))
    )
  )
  (nets
    (net (code "1") (name "/ADC") (class "Default")
      (node (ref "U4") (pin "25") (pinfunction "ADC_25") (pintype "input"))
    )
    (net (code "2") (name "/DISP_CLK") (class "Default")
      (node (ref "CLK") (pin "T") (pinfunction "T_T") (pintype "bidirectional"))
      (node (ref "U4") (pin "11") (pinfunction "DISP_CLK_11") (pintype "output"))
    )
    (net (code "3") (name "/DISP_CS") (class "Default")
      (node (ref "CS") (pin "T") (pinfunction "T_T") (pintype "bidirectional"))
      (node (ref "U4") (pin "14") (pinfunction "DISP_CS_14") (pintype "output"))
    )
    (net (code "4") (name "/DISP_DATA") (class "Default")
      (node (ref "DATA") (pin "T") (pinfunction "T_T") (pintype "bidirectional"))
      (node (ref "U4") (pin "12") (pinfunction "DISP_DATA_12") (pintype "bidirectional"))
    )
    (net (code "5") (name "/DISP_D{slash}C") (class "Default")
      (node (ref "D/C") (pin "T") (pinfunction "T_T") (pintype "bidirectional"))
      (node (ref "U4") (pin "13") (pinfunction "DISP_D/C_13") (pintype "output"))
    )
    (net (code "6") (name "/GPIO11") (class "Default")
      (node (ref "U4") (pin "67") (pinfunction "GPIO11_67") (pintype "bidirectional"))
    )
    (net (code "7") (name "/GPIO12") (class "Default")
      (node (ref "U4") (pin "68") (pinfunction "GPIO12_68") (pintype "bidirectional"))
    )
    (net (code "8") (name "/LDBG_RX") (class "Default")
      (node (ref "DBRX") (pin "T") (pinfunction "T_T") (pintype "bidirectional"))
      (node (ref "U4") (pin "28") (pinfunction "DBG_RXD_28") (pintype "input"))
    )
    (net (code "9") (name "/LDBG_TX") (class "Default")
      (node (ref "DBTX") (pin "T") (pinfunction "T_T") (pintype "bidirectional"))
      (node (ref "U4") (pin "27") (pinfunction "DBG_TXD_27") (pintype "output"))
    )
    (net (code "10") (name "/LRXD") (class "Default")
      (node (ref "Q14") (pin "2") (pinfunction "S_2") (pintype "passive"))
      (node (ref "R26") (pin "3") (pinfunction "1_3") (pintype "passive"))
      (node (ref "U4") (pin "10") (pinfunction "RXD_10") (pintype "input"))
    )
    (net (code "11") (name "/LTXD") (class "Default")
      (node (ref "Q15") (pin "2") (pinfunction "S_2") (pintype "passive"))
      (node (ref "R26") (pin "4") (pinfunction "1_4") (pintype "passive"))
      (node (ref "U4") (pin "9") (pinfunction "TXD_9") (pintype "output"))
    )
    (net (code "12") (name "/PIO0_2{slash}SSEL0") (class "Default")
      (node (ref "J7") (pin "3") (pinfunction "3_3") (pintype "bidirectional"))
      (node (ref "U1") (pin "13") (pinfunction "PIO0_2_13") (pintype "bidirectional"))
    )
    (net (code "13") (name "/PIO0_7") (class "Default")
      (node (ref "J7") (pin "8") (pinfunction "8_8") (pintype "bidirectional"))
      (node (ref "U1") (pin "30") (pinfunction "PIO0_7_30") (pintype "bidirectional"))
    )
    (net (code "14") (name "/PIO0_8{slash}MISO0") (class "Default")
      (node (ref "J7") (pin "5") (pinfunction "5_5") (pintype "bidirectional"))
      (node (ref "U1") (pin "36") (pinfunction "PIO0_8_36") (pintype "bidirectional"))
    )
    (net (code "15") (name "/PIO0_9{slash}MOSI0") (class "Default")
      (node (ref "J7") (pin "4") (pinfunction "4_4") (pintype "bidirectional"))
      (node (ref "U1") (pin "37") (pinfunction "PIO0_9_37") (pintype "bidirectional"))
    )
    (net (code "16") (name "/PIO0_13") (class "Default")
      (node (ref "J10") (pin "3") (pinfunction "3_3") (pintype "bidirectional"))
      (node (ref "U1") (pin "45") (pinfunction "TDO/PIO0_13_45") (pintype "bidirectional"))
    )
    (net (code "17") (name "/PIO0_14") (class "Default")
      (node (ref "J10") (pin "4") (pinfunction "4_4") (pintype "bidirectional"))
      (node (ref "U1") (pin "46") (pinfunction "PIO0_14/~{TRST}_46") (pintype "bidirectional"))
    )
    (net (code "18") (name "/PIO0_16") (class "Default")
      (node (ref "J10") (pin "5") (pinfunction "5_5") (pintype "bidirectional"))
      (node (ref "U1") (pin "53") (pinfunction "PIO0_16_53") (pintype "bidirectional"))
    )
    (net (code "19") (name "/PIO0_17{slash}D2") (class "Default")
      (node (ref "J8") (pin "3") (pinfunction "3_3") (pintype "bidirectional"))
      (node (ref "U1") (pin "60") (pinfunction "PIO0_17_60") (pintype "bidirectional"))
    )
    (net (code "20") (name "/PIO0_18{slash}RX") (class "Default")
      (node (ref "J8") (pin "1") (pinfunction "1_1") (pintype "bidirectional"))
      (node (ref "U1") (pin "61") (pinfunction "PIO0_18_61") (pintype "bidirectional"))
    )
    (net (code "21") (name "/PIO0_19{slash}TX") (class "Default")
      (node (ref "J8") (pin "2") (pinfunction "2_2") (pintype "bidirectional"))
      (node (ref "U1") (pin "62") (pinfunction "PIO0_19_62") (pintype "bidirectional"))
    )
    (net (code "22") (name "/PIO0_22") (class "Default")
      (node (ref "J10") (pin "6") (pinfunction "6_6") (pintype "bidirectional"))
      (node (ref "U1") (pin "40") (pinfunction "PIO0_22_40") (pintype "bidirectional"))
    )
    (net (code "23") (name "/PIO1_4{slash}D8") (class "Default")
      (node (ref "J7") (pin "1") (pinfunction "1_1") (pintype "bidirectional"))
      (node (ref "U1") (pin "16") (pinfunction "PIO1_4_16") (pintype "bidirectional"))
    )
    (net (code "24") (name "/PIO1_5{slash}D7") (class "Default")
      (node (ref "J8") (pin "8") (pinfunction "8_8") (pintype "bidirectional"))
      (node (ref "U1") (pin "32") (pinfunction "PIO1_5_32") (pintype "bidirectional"))
    )
    (net (code "25") (name "/PIO1_16") (class "Default")
      (node (ref "J9") (pin "1") (pinfunction "1_1") (pintype "bidirectional"))
      (node (ref "U1") (pin "63") (pinfunction "PIO1_16_63") (pintype "bidirectional"))
    )
    (net (code "26") (name "/PIO1_17{slash}D3") (class "Default")
      (node (ref "J8") (pin "4") (pinfunction "4_4") (pintype "bidirectional"))
      (node (ref "U1") (pin "23") (pinfunction "PIO1_17_23") (pintype "bidirectional"))
    )
    (net (code "27") (name "/PIO1_18{slash}D4") (class "Default")
      (node (ref "J8") (pin "5") (pinfunction "5_5") (pintype "bidirectional"))
      (node (ref "U1") (pin "28") (pinfunction "PIO1_18_28") (pintype "bidirectional"))
    )
    (net (code "28") (name "/PIO1_23{slash}SSEL1") (class "Default")
      (node (ref "TF") (pin "2") (pinfunction "CS_2") (pintype "bidirectional"))
      (node (ref "U1") (pin "24") (pinfunction "PIO1_23_24") (pintype "bidirectional"))
    )
    (net (code "29") (name "/PIO1_24{slash}D5") (class "Default")
      (node (ref "J8") (pin "6") (pinfunction "6_6") (pintype "bidirectional"))
      (node (ref "U1") (pin "27") (pinfunction "PIO1_24_27") (pintype "bidirectional"))
    )
    (net (code "30") (name "/PIO1_25{slash}D6") (class "Default")
      (node (ref "J8") (pin "7") (pinfunction "7_7") (pintype "bidirectional"))
      (node (ref "U1") (pin "2") (pinfunction "PIO1_25_2") (pintype "bidirectional"))
    )
    (net (code "31") (name "/PIO1_26{slash}RXD") (class "Default")
      (node (ref "Q15") (pin "3") (pinfunction "D_3") (pintype "passive"))
      (node (ref "R26") (pin "2") (pinfunction "1_2") (pintype "passive"))
      (node (ref "U1") (pin "14") (pinfunction "PIO1_26_14") (pintype "bidirectional"))
    )
    (net (code "32") (name "/PIO1_27{slash}TXD") (class "Default")
      (node (ref "Q14") (pin "3") (pinfunction "D_3") (pintype "passive"))
      (node (ref "R26") (pin "1") (pinfunction "1_1") (pintype "passive"))
      (node (ref "U1") (pin "15") (pinfunction "PIO1_27_15") (pintype "bidirectional"))
    )
    (net (code "33") (name "/PIO1_28{slash}D9") (class "Default")
      (node (ref "J7") (pin "2") (pinfunction "2_2") (pintype "bidirectional"))
      (node (ref "U1") (pin "31") (pinfunction "PIO1_28_31") (pintype "bidirectional"))
    )
    (net (code "34") (name "/PIO1_29{slash}SCK0") (class "Default")
      (node (ref "J7") (pin "6") (pinfunction "6_6") (pintype "bidirectional"))
      (node (ref "U1") (pin "41") (pinfunction "PIO1_29_41") (pintype "bidirectional"))
    )
    (net (code "35") (name "/PWM1") (class "Default")
      (node (ref "U4") (pin "35") (pinfunction "PWM1_35") (pintype "output"))
    )
    (net (code "36") (name "/PWRKEY") (class "Default")
      (node (ref "PWRKEY") (pin "0A") (pinfunction "0A_0A") (pintype "bidirectional"))
      (node (ref "PWRKEY") (pin "0B") (pinfunction "0B_0B") (pintype "bidirectional"))
      (node (ref "Q13") (pin "3") (pinfunction "C_3") (pintype "passive"))
      (node (ref "U4") (pin "1") (pinfunction "PWRKEY_1") (pintype "input"))
    )
    (net (code "37") (name "/SIM_CLK") (class "Default")
      (node (ref "R32") (pin "2") (pinfunction "2_2") (pintype "passive"))
      (node (ref "U4") (pin "32") (pinfunction "SIM_CLK_32") (pintype "output"))
    )
    (net (code "38") (name "/SIM_DATA") (class "Default")
      (node (ref "R48") (pin "2") (pinfunction "2_2") (pintype "passive"))
      (node (ref "U4") (pin "31") (pinfunction "SIM_DATA_31") (pintype "bidirectional"))
    )
    (net (code "39") (name "/SIM_RST") (class "Default")
      (node (ref "R47") (pin "2") (pinfunction "2_2") (pintype "passive"))
      (node (ref "U4") (pin "33") (pinfunction "SIM_RST_33") (pintype "output"))
    )
    (net (code "40") (name "/SIM_VDD") (class "Default")
      (node (ref "C44") (pin "2") (pinfunction "2_2") (pintype "passive"))
      (node (ref "C48") (pin "2") (pinfunction "2_2") (pintype "passive"))
      (node (ref "D14") (pin "2") (pinfunction "2_2") (pintype "bidirectional"))
      (node (ref "SIM") (pin "1") (pinfunction "VCC_1") (pintype "bidirectional"))
      (node (ref "SIM") (pin "5") (pinfunction "VPP_5") (pintype "bidirectional"))
      (node (ref "TP10") (pin "T") (pinfunction "T_T") (pintype "bidirectional"))
      (node (ref "U4") (pin "30") (pinfunction "SIM_VDD_30") (pintype "output"))
    )
    (net (code "41") (name "/VDD_EXT") (class "Default")
      (node (ref "C29") (pin "1") (pinfunction "1_1") (pintype "passive"))
      (node (ref "Q14") (pin "1") (pinfunction "G_1") (pintype "passive"))
      (node (ref "Q15") (pin "1") (pinfunction "G_1") (pintype "passive"))
      (node (ref "R26") (pin "5") (pinfunction "2_5") (pintype "passive"))
      (node (ref "R26") (pin "6") (pinfunction "2_6") (pintype "passive"))
      (node (ref "U4") (pin "15") (pinfunction "VDD_EXT_15") (pintype "output"))
    )
    (net (code "42") (name "/VRTC") (class "Default")
      (node (ref "C51") (pin "2") (pinfunction "2_2") (pintype "passive"))
      (node (ref "U4") (pin "26") (pinfunction "VRTC_26") (pintype "bidirectional"))
    )
    (net (code "43") (name "/XTALIN") (class "Default")
      (node (ref "C2") (pin "2") (pinfunction "2_2") (pintype "passive"))
      (node (ref "R5") (pin "2") (pinfunction "2_2") (pintype "passive"))
      (node (ref "U1") (pin "8") (pinfunction "XTALIN_8") (pintype "bidirectional"))
      (node (ref "X1") (pin "2") (pinfunction "2_2") (pintype "passive"))
    )
    (net (code "44") (name "/XTALOUT") (class "Default")
      (node (ref "C3") (pin "2") (pinfunction "2_2") (pintype "passive"))
      (node (ref "R5") (pin "1") (pinfunction "1_1") (pintype "passive"))
      (node (ref "U1") (pin "9") (pinfunction "XTALOUT_9") (pintype "bidirectional"))
      (node (ref "X1") (pin "1") (pinfunction "1_1") (pintype "passive"))
    )
    (net (code "45") (name "GND_POWER") (class "Default")
      (node (ref "ADC") (pin "4") (pinfunction "4_4") (pintype "bidirectional"))
      (node (ref "ANT1") (pin "GND1") (pinfunction "GND1_GND1") (pintype "bidirectional"))
      (node (ref "ANT1") (pin "GND2") (pinfunction "GND2_GND2") (pintype "bidirectional"))
      (node (ref "ANT1") (pin "GND3") (pinfunction "GND3_GND3") (pintype "bidirectional"))
      (node (ref "BAT") (pin "2") (pinfunction "P$2_2") (pintype "bidirectional"))
      (node (ref "BAT1") (pin "-") (pinfunction "-_-") (pintype "bidirectional"))
      (node (ref "C1") (pin "-") (pinfunction "-_-") (pintype "passive"))
      (node (ref "C10") (pin "1") (pinfunction "1_1") (pintype "passive"))
      (node (ref "C11") (pin "1") (pinfunction "1_1") (pintype "passive"))
      (node (ref "C12") (pin "1") (pinfunction "1_1") (pintype "passive"))
      (node (ref "C13") (pin "1") (pinfunction "1_1") (pintype "passive"))
      (node (ref "C14") (pin "1") (pinfunction "1_1") (pintype "passive"))
      (node (ref "C15") (pin "1") (pinfunction "1_1") (pintype "passive"))
      (node (ref "C16") (pin "2") (pinfunction "2_2") (pintype "passive"))
      (node (ref "C18") (pin "2") (pinfunction "2_2") (pintype "passive"))
      (node (ref "C19") (pin "1") (pinfunction "1_1") (pintype "passive"))
      (node (ref "C2") (pin "1") (pinfunction "1_1") (pintype "passive"))
      (node (ref "C20") (pin "1") (pinfunction "1_1") (pintype "passive"))
      (node (ref "C21") (pin "1") (pinfunction "1_1") (pintype "passive"))
      (node (ref "C22") (pin "1") (pinfunction "1_1") (pintype "passive"))
      (node (ref "C23") (pin "1") (pinfunction "1_1") (pintype "passive"))
      (node (ref "C24") (pin "1") (pinfunction "1_1") (pintype "passive"))
      (node (ref "C25") (pin "1") (pinfunction "1_1") (pintype "passive"))
      (node (ref "C26") (pin "-") (pinfunction "-_-") (pintype "passive"))
      (node (ref "C27") (pin "1") (pinfunction "1_1") (pintype "passive"))
      (node (ref "C28") (pin "2") (pinfunction "2_2") (pintype "passive"))
      (node (ref "C29") (pin "2") (pinfunction "2_2") (pintype "passive"))
      (node (ref "C3") (pin "1") (pinfunction "1_1") (pintype "passive"))
      (node (ref "C30") (pin "-") (pinfunction "-_-") (pintype "passive"))
      (node (ref "C31") (pin "1") (pinfunction "1_1") (pintype "passive"))
      (node (ref "C36") (pin "-") (pinfunction "-_-") (pintype "passive"))
      (node (ref "C37") (pin "1") (pinfunction "1_1") (pintype "passive"))
      (node (ref "C44") (pin "1") (pinfunction "1_1") (pintype "passive"))
      (node (ref "C45") (pin "1") (pinfunction "1_1") (pintype "passive"))
      (node (ref "C46") (pin "1") (pinfunction "1_1") (pintype "passive"))
      (node (ref "C47") (pin "1") (pinfunction "1_1") (pintype "passive"))
      (node (ref "C48") (pin "1") (pinfunction "1_1") (pintype "passive"))
      (node (ref "C49") (pin "-") (pinfunction "-_-") (pintype "passive"))
      (node (ref "C5") (pin "1") (pinfunction "1_1") (pintype "passive"))
      (node (ref "C50") (pin "2") (pinfunction "2_2") (pintype "passive"))
      (node (ref "C51") (pin "1") (pinfunction "1_1") (pintype "passive"))
      (node (ref "C52") (pin "1") (pinfunction "1_1") (pintype "passive"))
      (node (ref "C54") (pin "2") (pinfunction "2_2") (pintype "passive"))
      (node (ref "C55") (pin "2") (pinfunction "2_2") (pintype "passive"))
      (node (ref "C56") (pin "1") (pinfunction "1_1") (pintype "passive"))
      (node (ref "C58") (pin "1") (pinfunction "1_1") (pintype "passive"))
      (node (ref "C59") (pin "1") (pinfunction "1_1") (pintype "passive"))
      (node (ref "C6") (pin "1") (pinfunction "1_1") (pintype "passive"))
      (node (ref "C64") (pin "1") (pinfunction "1_1") (pintype "passive"))
      (node (ref "C65") (pin "1") (pinfunction "1_1") (pintype "passive"))
      (node (ref "C7") (pin "-") (pinfunction "-_-") (pintype "passive"))
      (node (ref "C8") (pin "1") (pinfunction "1_1") (pintype "passive"))
      (node (ref "C9") (pin "1") (pinfunction "1_1") (pintype "passive"))
      (node (ref "D12") (pin "1") (pinfunction "1_1") (pintype "bidirectional"))
      (node (ref "D13") (pin "3") (pinfunction "3_3") (pintype "bidirectional"))
      (node (ref "D14") (pin "3") (pinfunction "3_3") (pintype "bidirectional"))
      (node (ref "D16") (pin "3") (pinfunction "3_3") (pintype "bidirectional"))
      (node (ref "D17") (pin "+") (pinfunction "+_+") (pintype "passive"))
      (node (ref "D24") (pin "1") (pinfunction "1_1") (pintype "bidirectional"))
      (node (ref "D28") (pin "3") (pinfunction "3_3") (pintype "bidirectional"))
      (node (ref "D29") (pin "3") (pinfunction "3_3") (pintype "bidirectional"))
      (node (ref "D30") (pin "3") (pinfunction "3_3") (pintype "bidirectional"))
      (node (ref "D8") (pin "1") (pinfunction "1_1") (pintype "bidirectional"))
      (node (ref "I2C") (pin "4") (pinfunction "4_4") (pintype "bidirectional"))
      (node (ref "J2") (pin "5") (pinfunction "GND_5") (pintype "bidirectional"))
      (node (ref "J2") (pin "S1") (pinfunction "GND_S1") (pintype "bidirectional"))
      (node (ref "J2") (pin "S2") (pinfunction "GND_S2") (pintype "bidirectional"))
      (node (ref "J2") (pin "S3") (pinfunction "GND_S3") (pintype "bidirectional"))
      (node (ref "J2") (pin "S4") (pinfunction "GND_S4") (pintype "bidirectional"))
      (node (ref "J2") (pin "S5") (pinfunction "GND_S5") (pintype "bidirectional"))
      (node (ref "J2") (pin "S6") (pinfunction "GND_S6") (pintype "bidirectional"))
      (node (ref "J7") (pin "7") (pinfunction "7_7") (pintype "bidirectional"))
      (node (ref "J9") (pin "6") (pinfunction "6_6") (pintype "bidirectional"))
      (node (ref "J9") (pin "7") (pinfunction "7_7") (pintype "bidirectional"))
      (node (ref "Q11") (pin "3") (pinfunction "D_3") (pintype "passive"))
      (node (ref "Q12") (pin "2") (pinfunction "E_2") (pintype "passive"))
      (node (ref "Q13") (pin "2") (pinfunction "E_2") (pintype "passive"))
      (node (ref "Q4") (pin "2") (pinfunction "S_2") (pintype "passive"))
      (node (ref "Q7") (pin "2") (pinfunction "S_2") (pintype "passive"))
      (node (ref "Q8") (pin "2") (pinfunction "E_2") (pintype "passive"))
      (node (ref "R17") (pin "2") (pinfunction "2_2") (pintype "passive"))
      (node (ref "R21") (pin "1") (pinfunction "1_1") (pintype "passive"))
      (node (ref "R29") (pin "1") (pinfunction "1_1") (pintype "passive"))
      (node (ref "R3") (pin "2") (pinfunction "2_2") (pintype "passive"))
      (node (ref "R33") (pin "1") (pinfunction "1_1") (pintype "passive"))
      (node (ref "R37") (pin "5") (pinfunction "2_5") (pintype "passive"))
      (node (ref "R37") (pin "6") (pinfunction "2_6") (pintype "passive"))
      (node (ref "R37") (pin "7") (pinfunction "2_7") (pintype "passive"))
      (node (ref "R37") (pin "8") (pinfunction "2_8") (pintype "passive"))
      (node (ref "R56") (pin "1") (pinfunction "1_1") (pintype "passive"))
      (node (ref "R64") (pin "2") (pinfunction "2_2") (pintype "passive"))
      (node (ref "R68") (pin "2") (pinfunction "2_2") (pintype "passive"))
      (node (ref "R73") (pin "2") (pinfunction "2_2") (pintype "passive"))
      (node (ref "RESET") (pin "1A") (pinfunction "1A_1A") (pintype "bidirectional"))
      (node (ref "RESET") (pin "1B") (pinfunction "1B_1B") (pintype "bidirectional"))
      (node (ref "SIM") (pin "6") (pinfunction "GND_6") (pintype "bidirectional"))
      (node (ref "SIM") (pin "P1") (pinfunction "7_P1") (pintype "bidirectional"))
      (node (ref "SIM") (pin "P2") (pinfunction "8_P2") (pintype "bidirectional"))
      (node (ref "SOLAR") (pin "2") (pinfunction "P$2_2") (pintype "bidirectional"))
      (node (ref "SPI") (pin "4") (pinfunction "4_4") (pintype "bidirectional"))
      (node (ref "SWD") (pin "4") (pinfunction "P$4_4") (pintype "bidirectional"))
      (node (ref "TF") (pin "6") (pinfunction "VSS_6") (pintype "bidirectional"))
      (node (ref "TF") (pin "G1") (pinfunction "G1_G1") (pintype "bidirectional"))
      (node (ref "TF") (pin "G2") (pinfunction "G2_G2") (pintype "bidirectional"))
      (node (ref "TF") (pin "G3") (pinfunction "G3_G3") (pintype "bidirectional"))
      (node (ref "TF") (pin "G4") (pinfunction "G4_G4") (pintype "bidirectional"))
      (node (ref "TP11") (pin "T") (pinfunction "T_T") (pintype "bidirectional"))
      (node (ref "U1") (pin "54") (pinfunction "VSS_54") (pintype "bidirectional"))
      (node (ref "U1") (pin "7") (pinfunction "VSS_7") (pintype "bidirectional"))
      (node (ref "U2") (pin "1") (pinfunction "TEMP_1") (pintype "input"))
      (node (ref "U2") (pin "3") (pinfunction "GND_3") (pintype "power_in"))
      (node (ref "U2") (pin "HEAT") (pinfunction "H_HEAT") (pintype "bidirectional"))
      (node (ref "U3") (pin "4") (pinfunction "GND_4") (pintype "bidirectional"))
      (node (ref "U4") (pin "17") (pinfunction "GND_17") (pintype "power_in"))
      (node (ref "U4") (pin "18") (pinfunction "GND_18") (pintype "power_in"))
      (node (ref "U4") (pin "29") (pinfunction "GND_29") (pintype "power_in"))
      (node (ref "U4") (pin "39") (pinfunction "GND_39") (pintype "power_in"))
      (node (ref "U4") (pin "45") (pinfunction "GND_45") (pintype "power_in"))
      (node (ref "U4") (pin "46") (pinfunction "GND_46") (pintype "power_in"))
      (node (ref "U4") (pin "53") (pinfunction "GND_53") (pintype "power_in"))
      (node (ref "U4") (pin "54") (pinfunction "GND_54") (pintype "power_in"))
      (node (ref "U4") (pin "58") (pinfunction "GND_58") (pintype "power_in"))
      (node (ref "U4") (pin "59") (pinfunction "GND_59") (pintype "power_in"))
      (node (ref "U4") (pin "61") (pinfunction "GND_61") (pintype "power_in"))
      (node (ref "U4") (pin "62") (pinfunction "GND_62") (pintype "power_in"))
      (node (ref "U4") (pin "63") (pinfunction "GND_63") (pintype "power_in"))
      (node (ref "U4") (pin "64") (pinfunction "GND_64") (pintype "power_in"))
      (node (ref "U4") (pin "65") (pinfunction "GND_65") (pintype "power_in"))
      (node (ref "U5") (pin "2") (pinfunction "GND_2") (pintype "power_in"))
      (node (ref "UART") (pin "4") (pinfunction "4_4") (pintype "bidirectional"))
    )
    (net (code "46") (name "Net-(ANT1-PadD)") (class "Default")
      (node (ref "ANT1") (pin "D") (pinfunction "D_D") (pintype "bidirectional"))
      (node (ref "C59") (pin "2") (pinfunction "2_2") (pintype "passive"))
      (node (ref "R69") (pin "1") (pinfunction "1_1") (pintype "passive"))
    )
    (net (code "47") (name "Net-(C1-Pad+)") (class "Default")
      (node (ref "C1") (pin "+") (pinfunction "+_+") (pintype "passive"))
      (node (ref "C15") (pin "2") (pinfunction "2_2") (pintype "passive"))
      (node (ref "C17") (pin "2") (pinfunction "2_2") (pintype "passive"))
      (node (ref "L1") (pin "2") (pinfunction "2_2") (pintype "passive"))
      (node (ref "L2") (pin "1") (pinfunction "1_1") (pintype "passive"))
      (node (ref "R6") (pin "2") (pinfunction "2_2") (pintype "passive"))
    )
    (net (code "48") (name "Net-(C21-Pad2)") (class "Default")
      (node (ref "C21") (pin "2") (pinfunction "2_2") (pintype "passive"))
      (node (ref "C4") (pin "2") (pinfunction "2_2") (pintype "passive"))
      (node (ref "D20") (pin "+") (pinfunction "+_+") (pintype "passive"))
      (node (ref "R12") (pin "2") (pinfunction "2_2") (pintype "passive"))
      (node (ref "R15") (pin "1") (pinfunction "1_1") (pintype "passive"))
    )
    (net (code "49") (name "Net-(D1-Pad-)") (class "Default")
      (node (ref "D1") (pin "-") (pinfunction "-_-") (pintype "passive"))
      (node (ref "R37") (pin "1") (pinfunction "1_1") (pintype "passive"))
    )
    (net (code "50") (name "Net-(D6--)") (class "Default")
      (node (ref "C8") (pin "2") (pinfunction "2_2") (pintype "passive"))
      (node (ref "D6") (pin "1") (pinfunction "-_1") (pintype "passive"))
      (node (ref "Q5") (pin "2") (pinfunction "S_2") (pintype "passive"))
      (node (ref "Q6") (pin "2") (pinfunction "S_2") (pintype "passive"))
      (node (ref "R43") (pin "1") (pinfunction "1_1") (pintype "passive"))
      (node (ref "R7") (pin "1") (pinfunction "1_1") (pintype "passive"))
    )
    (net (code "51") (name "Net-(D7--)") (class "Default")
      (node (ref "C36") (pin "+") (pinfunction "+_+") (pintype "passive"))
      (node (ref "D7") (pin "1") (pinfunction "-_1") (pintype "passive"))
      (node (ref "Q3") (pin "2") (pinfunction "S_2") (pintype "passive"))
      (node (ref "Q9") (pin "2") (pinfunction "S_2") (pintype "passive"))
      (node (ref "R18") (pin "2") (pinfunction "2_2") (pintype "passive"))
      (node (ref "R19") (pin "2") (pinfunction "2_2") (pintype "passive"))
      (node (ref "R42") (pin "1") (pinfunction "1_1") (pintype "passive"))
      (node (ref "U2") (pin "4") (pinfunction "VIN_4") (pintype "input"))
    )
    (net (code "52") (name "Net-(D9-Pad+)") (class "Default")
      (node (ref "D9") (pin "+") (pinfunction "+_+") (pintype "passive"))
      (node (ref "L3") (pin "2") (pinfunction "2_2") (pintype "passive"))
    )
    (net (code "53") (name "Net-(D11-Pad-)") (class "Default")
      (node (ref "D11") (pin "-") (pinfunction "-_-") (pintype "passive"))
      (node (ref "R35") (pin "1") (pinfunction "1_1") (pintype "passive"))
    )
    (net (code "54") (name "Net-(D29-Pad1)") (class "Default")
      (node (ref "D29") (pin "1") (pinfunction "1_1") (pintype "bidirectional"))
      (node (ref "L9") (pin "2") (pinfunction "2_2") (pintype "passive"))
      (node (ref "SPK1") (pin "1") (pinfunction "1_1") (pintype "bidirectional"))
    )
    (net (code "55") (name "Net-(D29-Pad2)") (class "Default")
      (node (ref "D29") (pin "2") (pinfunction "2_2") (pintype "bidirectional"))
      (node (ref "L10") (pin "2") (pinfunction "2_2") (pintype "passive"))
      (node (ref "SPK1") (pin "2") (pinfunction "2_2") (pintype "bidirectional"))
    )
    (net (code "56") (name "Net-(D30-Pad1)") (class "Default")
      (node (ref "D30") (pin "1") (pinfunction "1_1") (pintype "bidirectional"))
      (node (ref "L6") (pin "2") (pinfunction "2_2") (pintype "passive"))
      (node (ref "MIC1") (pin "2") (pinfunction "2_2") (pintype "bidirectional"))
    )
    (net (code "57") (name "Net-(D30-Pad2)") (class "Default")
      (node (ref "D30") (pin "2") (pinfunction "2_2") (pintype "bidirectional"))
      (node (ref "L11") (pin "2") (pinfunction "2_2") (pintype "passive"))
      (node (ref "MIC1") (pin "1") (pinfunction "1_1") (pintype "bidirectional"))
    )
    (net (code "58") (name "Net-(ISP-Pad+)") (class "Default")
      (node (ref "ISP") (pin "+") (pinfunction "+_+") (pintype "passive"))
      (node (ref "R24") (pin "2") (pinfunction "2_2") (pintype "passive"))
    )
    (net (code "59") (name "Net-(J2-DM)") (class "Default")
      (node (ref "D28") (pin "2") (pinfunction "2_2") (pintype "bidirectional"))
      (node (ref "J2") (pin "2") (pinfunction "DM_2") (pintype "bidirectional"))
      (node (ref "R23") (pin "1") (pinfunction "1_1") (pintype "passive"))
    )
    (net (code "60") (name "Net-(J2-DP)") (class "Default")
      (node (ref "D28") (pin "1") (pinfunction "1_1") (pintype "bidirectional"))
      (node (ref "J2") (pin "3") (pinfunction "DP_3") (pintype "bidirectional"))
      (node (ref "R11") (pin "1") (pinfunction "1_1") (pintype "passive"))
      (node (ref "R31") (pin "1") (pinfunction "1_1") (pintype "passive"))
    )
    (net (code "61") (name "Net-(J2-VCC)") (class "Default")
      (node (ref "F1") (pin "1") (pinfunction "1_1") (pintype "bidirectional"))
      (node (ref "J2") (pin "1") (pinfunction "VCC_1") (pintype "bidirectional"))
      (node (ref "TP1") (pin "T") (pinfunction "T_T") (pintype "bidirectional"))
    )
    (net (code "62") (name "Net-(JP-Pad2)") (class "Default")
      (node (ref "JP") (pin "2") (pinfunction "2_2") (pintype "passive"))
      (node (ref "R72") (pin "1") (pinfunction "1_1") (pintype "passive"))
    )
    (net (code "63") (name "Net-(NET-Pad-)") (class "Default")
      (node (ref "NET") (pin "-") (pinfunction "-_-") (pintype "passive"))
      (node (ref "R62") (pin "1") (pinfunction "1_1") (pintype "passive"))
    )
    (net (code "64") (name "Net-(Q1-D)") (class "Default")
      (node (ref "ADC") (pin "3") (pinfunction "3_3") (pintype "bidirectional"))
      (node (ref "C19") (pin "2") (pinfunction "2_2") (pintype "passive"))
      (node (ref "C20") (pin "2") (pinfunction "2_2") (pintype "passive"))
      (node (ref "C25") (pin "2") (pinfunction "2_2") (pintype "passive"))
      (node (ref "I2C") (pin "3") (pinfunction "3_3") (pintype "bidirectional"))
      (node (ref "Q1") (pin "3") (pinfunction "D_3") (pintype "passive"))
      (node (ref "TP6") (pin "T") (pinfunction "T_T") (pintype "bidirectional"))
      (node (ref "UART") (pin "3") (pinfunction "3_3") (pintype "bidirectional"))
    )
    (net (code "65") (name "Net-(Q1-G)") (class "Default")
      (node (ref "Q1") (pin "1") (pinfunction "G_1") (pintype "passive"))
      (node (ref "R30") (pin "1") (pinfunction "1_1") (pintype "passive"))
      (node (ref "R9") (pin "1") (pinfunction "1_1") (pintype "passive"))
    )
    (net (code "66") (name "Net-(Q2-D)") (class "Default")
      (node (ref "Q2") (pin "3") (pinfunction "D_3") (pintype "passive"))
      (node (ref "R11") (pin "2") (pinfunction "2_2") (pintype "passive"))
    )
    (net (code "67") (name "Net-(Q3-G)") (class "Default")
      (node (ref "Q3") (pin "1") (pinfunction "G_1") (pintype "passive"))
      (node (ref "Q4") (pin "3") (pinfunction "D_3") (pintype "passive"))
      (node (ref "R42") (pin "2") (pinfunction "2_2") (pintype "passive"))
    )
    (net (code "68") (name "Net-(Q4-G)") (class "Default")
      (node (ref "Q4") (pin "1") (pinfunction "G_1") (pintype "passive"))
      (node (ref "R8") (pin "1") (pinfunction "1_1") (pintype "passive"))
    )
    (net (code "69") (name "Net-(Q5-G)") (class "Default")
      (node (ref "Q5") (pin "1") (pinfunction "G_1") (pintype "passive"))
      (node (ref "R57") (pin "2") (pinfunction "2_2") (pintype "passive"))
      (node (ref "R7") (pin "2") (pinfunction "2_2") (pintype "passive"))
    )
    (net (code "70") (name "Net-(Q6-G)") (class "Default")
      (node (ref "Q6") (pin "1") (pinfunction "G_1") (pintype "passive"))
      (node (ref "R2") (pin "1") (pinfunction "1_1") (pintype "passive"))
    )
    (net (code "71") (name "Net-(Q7-D)") (class "Default")
      (node (ref "Q7") (pin "3") (pinfunction "D_3") (pintype "passive"))
      (node (ref "R57") (pin "1") (pinfunction "1_1") (pintype "passive"))
    )
    (net (code "72") (name "Net-(Q8-B)") (class "Default")
      (node (ref "Q8") (pin "1") (pinfunction "B_1") (pintype "passive"))
      (node (ref "R63") (pin "2") (pinfunction "2_2") (pintype "passive"))
      (node (ref "R64") (pin "1") (pinfunction "1_1") (pintype "passive"))
    )
    (net (code "73") (name "Net-(Q8-C)") (class "Default")
      (node (ref "Q8") (pin "3") (pinfunction "C_3") (pintype "passive"))
      (node (ref "R62") (pin "2") (pinfunction "2_2") (pintype "passive"))
    )
    (net (code "74") (name "Net-(Q9-G)") (class "Default")
      (node (ref "Q9") (pin "1") (pinfunction "G_1") (pintype "passive"))
      (node (ref "R28") (pin "1") (pinfunction "1_1") (pintype "passive"))
    )
    (net (code "75") (name "Net-(Q10-D)") (class "Default")
      (node (ref "Q10") (pin "3") (pinfunction "D_3") (pintype "passive"))
      (node (ref "Q7") (pin "1") (pinfunction "G_1") (pintype "passive"))
      (node (ref "R56") (pin "2") (pinfunction "2_2") (pintype "passive"))
    )
    (net (code "76") (name "Net-(Q10-G)") (class "Default")
      (node (ref "Q10") (pin "1") (pinfunction "G_1") (pintype "passive"))
      (node (ref "R22") (pin "1") (pinfunction "1_1") (pintype "passive"))
      (node (ref "R58") (pin "1") (pinfunction "1_1") (pintype "passive"))
    )
    (net (code "77") (name "Net-(Q11-G)") (class "Default")
      (node (ref "Q11") (pin "1") (pinfunction "G_1") (pintype "passive"))
      (node (ref "R25") (pin "2") (pinfunction "2_2") (pintype "passive"))
      (node (ref "R34") (pin "2") (pinfunction "2_2") (pintype "passive"))
    )
    (net (code "78") (name "Net-(Q11-S)") (class "Default")
      (node (ref "ISP") (pin "-") (pinfunction "-_-") (pintype "passive"))
      (node (ref "Q11") (pin "2") (pinfunction "S_2") (pintype "passive"))
    )
    (net (code "79") (name "Net-(Q12-B)") (class "Default")
      (node (ref "Q12") (pin "1") (pinfunction "B_1") (pintype "passive"))
      (node (ref "R67") (pin "2") (pinfunction "2_2") (pintype "passive"))
      (node (ref "R68") (pin "1") (pinfunction "1_1") (pintype "passive"))
    )
    (net (code "80") (name "Net-(Q12-C)") (class "Default")
      (node (ref "Q12") (pin "3") (pinfunction "C_3") (pintype "passive"))
      (node (ref "R66") (pin "2") (pinfunction "2_2") (pintype "passive"))
    )
    (net (code "81") (name "Net-(Q13-B)") (class "Default")
      (node (ref "Q13") (pin "1") (pinfunction "B_1") (pintype "passive"))
      (node (ref "R72") (pin "2") (pinfunction "2_2") (pintype "passive"))
      (node (ref "R73") (pin "1") (pinfunction "1_1") (pintype "passive"))
    )
    (net (code "82") (name "Net-(R37B-1)") (class "Default")
      (node (ref "D2") (pin "-") (pinfunction "-_-") (pintype "passive"))
      (node (ref "R37") (pin "2") (pinfunction "1_2") (pintype "passive"))
    )
    (net (code "83") (name "Net-(R37C-1)") (class "Default")
      (node (ref "D3") (pin "-") (pinfunction "-_-") (pintype "passive"))
      (node (ref "R37") (pin "3") (pinfunction "1_3") (pintype "passive"))
    )
    (net (code "84") (name "Net-(R37D-1)") (class "Default")
      (node (ref "D4") (pin "-") (pinfunction "-_-") (pintype "passive"))
      (node (ref "R37") (pin "4") (pinfunction "1_4") (pintype "passive"))
    )
    (net (code "85") (name "Net-(R45-Pad1)") (class "Default")
      (node (ref "R45") (pin "1") (pinfunction "1_1") (pintype "passive"))
      (node (ref "SPI") (pin "6") (pinfunction "6_6") (pintype "bidirectional"))
    )
    (net (code "86") (name "Net-(R66-Pad1)") (class "Default")
      (node (ref "R66") (pin "1") (pinfunction "1_1") (pintype "passive"))
      (node (ref "STA") (pin "-") (pinfunction "-_-") (pintype "passive"))
    )
    (net (code "87") (name "Net-(SIM-CLK)") (class "Default")
      (node (ref "C46") (pin "2") (pinfunction "2_2") (pintype "passive"))
      (node (ref "D13") (pin "2") (pinfunction "2_2") (pintype "bidirectional"))
      (node (ref "R32") (pin "1") (pinfunction "1_1") (pintype "passive"))
      (node (ref "SIM") (pin "3") (pinfunction "CLK_3") (pintype "bidirectional"))
      (node (ref "TP8") (pin "T") (pinfunction "T_T") (pintype "bidirectional"))
    )
    (net (code "88") (name "Net-(SIM-I{slash}O)") (class "Default")
      (node (ref "C47") (pin "2") (pinfunction "2_2") (pintype "passive"))
      (node (ref "D14") (pin "1") (pinfunction "1_1") (pintype "bidirectional"))
      (node (ref "R48") (pin "1") (pinfunction "1_1") (pintype "passive"))
      (node (ref "SIM") (pin "4") (pinfunction "I/O_4") (pintype "bidirectional"))
      (node (ref "TP9") (pin "T") (pinfunction "T_T") (pintype "bidirectional"))
    )
    (net (code "89") (name "Net-(SIM-RST)") (class "Default")
      (node (ref "C45") (pin "2") (pinfunction "2_2") (pintype "passive"))
      (node (ref "D13") (pin "1") (pinfunction "1_1") (pintype "bidirectional"))
      (node (ref "R47") (pin "1") (pinfunction "1_1") (pintype "passive"))
      (node (ref "SIM") (pin "2") (pinfunction "RST_2") (pintype "bidirectional"))
      (node (ref "TP5") (pin "T") (pinfunction "T_T") (pintype "bidirectional"))
    )
    (net (code "90") (name "Net-(SWD-P$1)") (class "Default")
      (node (ref "D27") (pin "-") (pinfunction "-_-") (pintype "passive"))
      (node (ref "SWD") (pin "1") (pinfunction "P$1_1") (pintype "bidirectional"))
    )
    (net (code "91") (name "Net-(U2-CHRG)") (class "Default")
      (node (ref "R4") (pin "2") (pinfunction "2_2") (pintype "passive"))
      (node (ref "U2") (pin "7") (pinfunction "CHRG_7") (pintype "bidirectional"))
    )
    (net (code "92") (name "Net-(U2-DONE)") (class "Default")
      (node (ref "R54") (pin "2") (pinfunction "2_2") (pintype "passive"))
      (node (ref "U2") (pin "6") (pinfunction "DONE_6") (pintype "bidirectional"))
    )
    (net (code "93") (name "Net-(U2-ISET)") (class "Default")
      (node (ref "R33") (pin "2") (pinfunction "2_2") (pintype "passive"))
      (node (ref "U2") (pin "2") (pinfunction "ISET_2") (pintype "bidirectional"))
    )
    (net (code "94") (name "Net-(U3-VCC)") (class "Default")
      (node (ref "BAT1") (pin "+") (pinfunction "+_+") (pintype "bidirectional"))
      (node (ref "C16") (pin "1") (pinfunction "1_1") (pintype "passive"))
      (node (ref "R35") (pin "2") (pinfunction "2_2") (pintype "passive"))
      (node (ref "U3") (pin "8") (pinfunction "VCC_8") (pintype "bidirectional"))
    )
    (net (code "95") (name "Net-(U3-X1)") (class "Default")
      (node (ref "C9") (pin "2") (pinfunction "2_2") (pintype "passive"))
      (node (ref "U3") (pin "1") (pinfunction "X1_1") (pintype "bidirectional"))
      (node (ref "X2") (pin "2") (pinfunction "2_2") (pintype "passive"))
    )
    (net (code "96") (name "Net-(U3-X2)") (class "Default")
      (node (ref "C14") (pin "2") (pinfunction "2_2") (pintype "passive"))
      (node (ref "U3") (pin "2") (pinfunction "X2_2") (pintype "bidirectional"))
      (node (ref "X2") (pin "1") (pinfunction "1_1") (pintype "passive"))
    )
    (net (code "97") (name "Net-(U4-MIC_N)") (class "Default")
      (node (ref "C18") (pin "1") (pinfunction "1_1") (pintype "passive"))
      (node (ref "C50") (pin "1") (pinfunction "1_1") (pintype "passive"))
      (node (ref "C62") (pin "2") (pinfunction "2_2") (pintype "passive"))
      (node (ref "C63") (pin "1") (pinfunction "1_1") (pintype "passive"))
      (node (ref "L6") (pin "1") (pinfunction "1_1") (pintype "passive"))
      (node (ref "U4") (pin "20") (pinfunction "MIC_N_20") (pintype "input"))
    )
    (net (code "98") (name "Net-(U4-MIC_P)") (class "Default")
      (node (ref "C62") (pin "1") (pinfunction "1_1") (pintype "passive"))
      (node (ref "C63") (pin "2") (pinfunction "2_2") (pintype "passive"))
      (node (ref "C64") (pin "2") (pinfunction "2_2") (pintype "passive"))
      (node (ref "C65") (pin "2") (pinfunction "2_2") (pintype "passive"))
      (node (ref "L11") (pin "1") (pinfunction "1_1") (pintype "passive"))
      (node (ref "U4") (pin "19") (pinfunction "MIC_P_19") (pintype "input"))
    )
    (net (code "99") (name "Net-(U4-NETLIGHT)") (class "Default")
      (node (ref "R63") (pin "1") (pinfunction "1_1") (pintype "passive"))
      (node (ref "U4") (pin "52") (pinfunction "NETLIGHT_52") (pintype "output"))
    )
    (net (code "100") (name "Net-(U4-PWRKEY_OUT)") (class "Default")
      (node (ref "PWRKEY") (pin "1A") (pinfunction "1A_1A") (pintype "bidirectional"))
      (node (ref "PWRKEY") (pin "1B") (pinfunction "1B_1B") (pintype "bidirectional"))
      (node (ref "U4") (pin "2") (pinfunction "PWRKEY_OUT_2") (pintype "output"))
    )
    (net (code "101") (name "Net-(U4-RF_ANT)") (class "Default")
      (node (ref "C58") (pin "2") (pinfunction "2_2") (pintype "passive"))
      (node (ref "R69") (pin "2") (pinfunction "2_2") (pintype "passive"))
      (node (ref "U4") (pin "60") (pinfunction "RF_ANT_60") (pintype "bidirectional"))
    )
    (net (code "102") (name "Net-(U4-SPK_N)") (class "Default")
      (node (ref "C52") (pin "2") (pinfunction "2_2") (pintype "passive"))
      (node (ref "C53") (pin "1") (pinfunction "1_1") (pintype "passive"))
      (node (ref "C56") (pin "2") (pinfunction "2_2") (pintype "passive"))
      (node (ref "C57") (pin "1") (pinfunction "1_1") (pintype "passive"))
      (node (ref "L9") (pin "1") (pinfunction "1_1") (pintype "passive"))
      (node (ref "U4") (pin "22") (pinfunction "SPK_N_22") (pintype "output"))
    )
    (net (code "103") (name "Net-(U4-SPK_P)") (class "Default")
      (node (ref "C53") (pin "2") (pinfunction "2_2") (pintype "passive"))
      (node (ref "C54") (pin "1") (pinfunction "1_1") (pintype "passive"))
      (node (ref "C55") (pin "1") (pinfunction "1_1") (pintype "passive"))
      (node (ref "C57") (pin "2") (pinfunction "2_2") (pintype "passive"))
      (node (ref "L10") (pin "1") (pinfunction "1_1") (pintype "passive"))
      (node (ref "U4") (pin "21") (pinfunction "SPK_P_21") (pintype "output"))
    )
    (net (code "104") (name "Net-(U4-STATUS)") (class "Default")
      (node (ref "R67") (pin "1") (pinfunction "1_1") (pintype "passive"))
      (node (ref "U4") (pin "66") (pinfunction "STATUS_66") (pintype "output"))
    )
    (net (code "105") (name "Net-(U5-SW)") (class "Default")
      (node (ref "D17") (pin "-") (pinfunction "-_-") (pintype "passive"))
      (node (ref "L1") (pin "1") (pinfunction "1_1") (pintype "passive"))
      (node (ref "U5") (pin "3") (pinfunction "SW_3") (pintype "bidirectional"))
    )
    (net (code "106") (name "Net-(U5-VFB)") (class "Default")
      (node (ref "C17") (pin "1") (pinfunction "1_1") (pintype "passive"))
      (node (ref "R17") (pin "1") (pinfunction "1_1") (pintype "passive"))
      (node (ref "R6") (pin "1") (pinfunction "1_1") (pintype "passive"))
      (node (ref "U5") (pin "5") (pinfunction "VFB_5") (pintype "input"))
    )
    (net (code "107") (name "PIO0_0{slash}RES") (class "Default")
      (node (ref "R15") (pin "2") (pinfunction "2_2") (pintype "passive"))
      (node (ref "U1") (pin "4") (pinfunction "PIO0_0/~{RESET}_4") (pintype "bidirectional"))
    )
    (net (code "108") (name "PIO0_1") (class "Default")
      (node (ref "R14") (pin "2") (pinfunction "2_2") (pintype "passive"))
      (node (ref "U1") (pin "5") (pinfunction "PIO0_1_5") (pintype "bidirectional"))
    )
    (net (code "109") (name "PIO0_3{slash}VBUS") (class "Default")
      (node (ref "R1") (pin "2") (pinfunction "2_2") (pintype "passive"))
      (node (ref "R3") (pin "1") (pinfunction "1_1") (pintype "passive"))
      (node (ref "U1") (pin "19") (pinfunction "PIO0_3_19") (pintype "bidirectional"))
    )
    (net (code "110") (name "PIO0_4{slash}SCL") (class "Default")
      (node (ref "I2C") (pin "1") (pinfunction "1_1") (pintype "bidirectional"))
      (node (ref "J7") (pin "10") (pinfunction "10_10") (pintype "bidirectional"))
      (node (ref "R50") (pin "1") (pinfunction "1_1") (pintype "passive"))
      (node (ref "U1") (pin "20") (pinfunction "PIO0_4_20") (pintype "bidirectional"))
      (node (ref "U3") (pin "6") (pinfunction "SCL_6") (pintype "bidirectional"))
    )
    (net (code "111") (name "PIO0_5{slash}SDA") (class "Default")
      (node (ref "I2C") (pin "2") (pinfunction "2_2") (pintype "bidirectional"))
      (node (ref "J7") (pin "9") (pinfunction "9_9") (pintype "bidirectional"))
      (node (ref "R49") (pin "1") (pinfunction "1_1") (pintype "passive"))
      (node (ref "U1") (pin "21") (pinfunction "PIO0_5_21") (pintype "bidirectional"))
      (node (ref "U3") (pin "5") (pinfunction "SDA_5") (pintype "bidirectional"))
    )
    (net (code "112") (name "PIO0_6") (class "Default")
      (node (ref "Q2") (pin "1") (pinfunction "G_1") (pintype "passive"))
      (node (ref "R25") (pin "1") (pinfunction "1_1") (pintype "passive"))
      (node (ref "U1") (pin "29") (pinfunction "PIO0_6_29") (pintype "bidirectional"))
    )
    (net (code "113") (name "PIO0_10{slash}SWCLK") (class "Default")
      (node (ref "R55") (pin "2") (pinfunction "2_2") (pintype "passive"))
      (node (ref "SWD") (pin "3") (pinfunction "P$3_3") (pintype "bidirectional"))
      (node (ref "U1") (pin "38") (pinfunction "SWCLK/PIO0_10_38") (pintype "bidirectional"))
    )
    (net (code "114") (name "PIO0_11") (class "Default")
      (node (ref "ADC") (pin "2") (pinfunction "2_2") (pintype "bidirectional"))
      (node (ref "J10") (pin "1") (pinfunction "1_1") (pintype "bidirectional"))
      (node (ref "U1") (pin "42") (pinfunction "TDI/PIO0_11_42") (pintype "bidirectional"))
    )
    (net (code "115") (name "PIO0_12") (class "Default")
      (node (ref "ADC") (pin "1") (pinfunction "1_1") (pintype "bidirectional"))
      (node (ref "J10") (pin "2") (pinfunction "2_2") (pintype "bidirectional"))
      (node (ref "U1") (pin "44") (pinfunction "TMS/PIO0_12_44") (pintype "bidirectional"))
    )
    (net (code "116") (name "PIO0_15{slash}SWDIO") (class "Default")
      (node (ref "R10") (pin "2") (pinfunction "2_2") (pintype "passive"))
      (node (ref "SWD") (pin "2") (pinfunction "P$2_2") (pintype "bidirectional"))
      (node (ref "U1") (pin "52") (pinfunction "SWDIO/PIO0_15_52") (pintype "bidirectional"))
    )
    (net (code "117") (name "PIO0_23") (class "Default")
      (node (ref "C37") (pin "2") (pinfunction "2_2") (pintype "passive"))
      (node (ref "R20") (pin "1") (pinfunction "1_1") (pintype "passive"))
      (node (ref "R21") (pin "2") (pinfunction "2_2") (pintype "passive"))
      (node (ref "U1") (pin "56") (pinfunction "PIO0_23_56") (pintype "bidirectional"))
    )
    (net (code "118") (name "PIO1_0") (class "Default")
      (node (ref "R18") (pin "1") (pinfunction "1_1") (pintype "passive"))
      (node (ref "R54") (pin "1") (pinfunction "1_1") (pintype "passive"))
      (node (ref "U1") (pin "1") (pinfunction "PIO1_0_1") (pintype "bidirectional"))
    )
    (net (code "119") (name "PIO1_1") (class "Default")
      (node (ref "R19") (pin "1") (pinfunction "1_1") (pintype "passive"))
      (node (ref "R4") (pin "1") (pinfunction "1_1") (pintype "passive"))
      (node (ref "U1") (pin "17") (pinfunction "PIO1_1_17") (pintype "bidirectional"))
    )
    (net (code "120") (name "PIO1_2") (class "Default")
      (node (ref "R22") (pin "2") (pinfunction "2_2") (pintype "passive"))
      (node (ref "U1") (pin "34") (pinfunction "PIO1_2_34") (pintype "bidirectional"))
    )
    (net (code "121") (name "PIO1_3") (class "Default")
      (node (ref "R30") (pin "2") (pinfunction "2_2") (pintype "passive"))
      (node (ref "U1") (pin "50") (pinfunction "PIO1_3_50") (pintype "bidirectional"))
    )
    (net (code "122") (name "PIO1_7") (class "Default")
      (node (ref "D16") (pin "2") (pinfunction "2_2") (pintype "bidirectional"))
      (node (ref "JP") (pin "1") (pinfunction "1_1") (pintype "passive"))
      (node (ref "U1") (pin "6") (pinfunction "PIO1_7_6") (pintype "bidirectional"))
    )
    (net (code "123") (name "PIO1_8") (class "Default")
      (node (ref "D1") (pin "+") (pinfunction "+_+") (pintype "passive"))
      (node (ref "U1") (pin "39") (pinfunction "PIO1_8_39") (pintype "bidirectional"))
    )
    (net (code "124") (name "PIO1_9") (class "Default")
      (node (ref "D4") (pin "+") (pinfunction "+_+") (pintype "passive"))
      (node (ref "U1") (pin "55") (pinfunction "PIO1_9_55") (pintype "bidirectional"))
    )
    (net (code "125") (name "PIO1_10") (class "Default")
      (node (ref "D3") (pin "+") (pinfunction "+_+") (pintype "passive"))
      (node (ref "U1") (pin "12") (pinfunction "PIO1_10_12") (pintype "bidirectional"))
    )
    (net (code "126") (name "PIO1_11") (class "Default")
      (node (ref "D2") (pin "+") (pinfunction "+_+") (pintype "passive"))
      (node (ref "U1") (pin "43") (pinfunction "PIO1_11_43") (pintype "bidirectional"))
    )
    (net (code "127") (name "PIO1_12") (class "Default")
      (node (ref "R51") (pin "1") (pinfunction "1_1") (pintype "passive"))
      (node (ref "U1") (pin "59") (pinfunction "PIO1_12_59") (pintype "bidirectional"))
      (node (ref "U3") (pin "7") (pinfunction "SQW/~{INTB}_7") (pintype "bidirectional"))
    )
    (net (code "128") (name "PIO1_13{slash}TX") (class "Default")
      (node (ref "U1") (pin "47") (pinfunction "PIO1_13_47") (pintype "bidirectional"))
      (node (ref "UART") (pin "2") (pinfunction "2_2") (pintype "bidirectional"))
    )
    (net (code "129") (name "PIO1_14{slash}RX") (class "Default")
      (node (ref "U1") (pin "49") (pinfunction "PIO1_14_49") (pintype "bidirectional"))
      (node (ref "UART") (pin "1") (pinfunction "1_1") (pintype "bidirectional"))
    )
    (net (code "130") (name "PIO1_19{slash}SSEL1") (class "Default")
      (node (ref "SPI") (pin "3") (pinfunction "3_3") (pintype "bidirectional"))
      (node (ref "U1") (pin "3") (pinfunction "PIO1_19_3") (pintype "bidirectional"))
    )
    (net (code "131") (name "PIO1_20{slash}SCK1") (class "Default")
      (node (ref "SPI") (pin "2") (pinfunction "2_2") (pintype "bidirectional"))
      (node (ref "TF") (pin "5") (pinfunction "SCLK_5") (pintype "bidirectional"))
      (node (ref "U1") (pin "18") (pinfunction "PIO1_20_18") (pintype "bidirectional"))
    )
    (net (code "132") (name "PIO1_21{slash}MISO1") (class "Default")
      (node (ref "SPI") (pin "1") (pinfunction "1_1") (pintype "bidirectional"))
      (node (ref "TF") (pin "7") (pinfunction "DO_7") (pintype "bidirectional"))
      (node (ref "U1") (pin "35") (pinfunction "PIO1_21_35") (pintype "bidirectional"))
    )
    (net (code "133") (name "PIO1_22{slash}MOSI1") (class "Default")
      (node (ref "SPI") (pin "5") (pinfunction "5_5") (pintype "bidirectional"))
      (node (ref "TF") (pin "3") (pinfunction "DI_3") (pintype "bidirectional"))
      (node (ref "U1") (pin "51") (pinfunction "PIO1_22_51") (pintype "bidirectional"))
    )
    (net (code "134") (name "RESET") (class "Default")
      (node (ref "C4") (pin "1") (pinfunction "1_1") (pintype "passive"))
      (node (ref "J9") (pin "3") (pinfunction "3_3") (pintype "bidirectional"))
      (node (ref "R13") (pin "2") (pinfunction "2_2") (pintype "passive"))
      (node (ref "R14") (pin "1") (pinfunction "1_1") (pintype "passive"))
      (node (ref "RESET") (pin "0A") (pinfunction "0A_0A") (pintype "bidirectional"))
      (node (ref "RESET") (pin "0B") (pinfunction "0B_0B") (pintype "bidirectional"))
    )
    (net (code "135") (name "USB_5V") (class "Default")
      (node (ref "C5") (pin "2") (pinfunction "2_2") (pintype "passive"))
      (node (ref "D12") (pin "2") (pinfunction "2_2") (pintype "bidirectional"))
      (node (ref "D5") (pin "+") (pinfunction "+_+") (pintype "passive"))
      (node (ref "D7") (pin "2") (pinfunction "+_2") (pintype "passive"))
      (node (ref "F1") (pin "2") (pinfunction "2_2") (pintype "bidirectional"))
      (node (ref "R1") (pin "1") (pinfunction "1_1") (pintype "passive"))
      (node (ref "R2") (pin "2") (pinfunction "2_2") (pintype "passive"))
      (node (ref "R28") (pin "2") (pinfunction "2_2") (pintype "passive"))
      (node (ref "R29") (pin "2") (pinfunction "2_2") (pintype "passive"))
      (node (ref "R8") (pin "2") (pinfunction "2_2") (pintype "passive"))
      (node (ref "TP2") (pin "T") (pinfunction "T_T") (pintype "bidirectional"))
    )
    (net (code "136") (name "USB_DM") (class "Default")
      (node (ref "R23") (pin "2") (pinfunction "2_2") (pintype "passive"))
      (node (ref "U1") (pin "25") (pinfunction "USB_DM_25") (pintype "bidirectional"))
    )
    (net (code "137") (name "USB_DP") (class "Default")
      (node (ref "R31") (pin "2") (pinfunction "2_2") (pintype "passive"))
      (node (ref "U1") (pin "26") (pinfunction "USB_DP_26") (pintype "bidirectional"))
    )
    (net (code "138") (name "VBAT_900") (class "Default")
      (node (ref "C22") (pin "2") (pinfunction "2_2") (pintype "passive"))
      (node (ref "C30") (pin "+") (pinfunction "+_+") (pintype "passive"))
      (node (ref "C31") (pin "2") (pinfunction "2_2") (pintype "passive"))
      (node (ref "C49") (pin "+") (pinfunction "+_+") (pintype "passive"))
      (node (ref "D16") (pin "1") (pinfunction "1_1") (pintype "bidirectional"))
      (node (ref "NET") (pin "+") (pinfunction "+_+") (pintype "passive"))
      (node (ref "Q5") (pin "3") (pinfunction "D_3") (pintype "passive"))
      (node (ref "STA") (pin "+") (pinfunction "+_+") (pintype "passive"))
      (node (ref "TP7") (pin "T") (pinfunction "T_T") (pintype "bidirectional"))
      (node (ref "U4") (pin "55") (pinfunction "VBAT_55") (pintype "power_in"))
      (node (ref "U4") (pin "56") (pinfunction "VBAT_56") (pintype "power_in"))
      (node (ref "U4") (pin "57") (pinfunction "VBAT_57") (pintype "power_in"))
    )
    (net (code "139") (name "VCC_3V3") (class "Default")
      (node (ref "C10") (pin "2") (pinfunction "2_2") (pintype "passive"))
      (node (ref "C11") (pin "2") (pinfunction "2_2") (pintype "passive"))
      (node (ref "C12") (pin "2") (pinfunction "2_2") (pintype "passive"))
      (node (ref "C13") (pin "2") (pinfunction "2_2") (pintype "passive"))
      (node (ref "C24") (pin "2") (pinfunction "2_2") (pintype "passive"))
      (node (ref "C28") (pin "1") (pinfunction "1_1") (pintype "passive"))
      (node (ref "C6") (pin "2") (pinfunction "2_2") (pintype "passive"))
      (node (ref "D11") (pin "+") (pinfunction "+_+") (pintype "passive"))
      (node (ref "D20") (pin "-") (pinfunction "-_-") (pintype "passive"))
      (node (ref "D27") (pin "+") (pinfunction "+_+") (pintype "passive"))
      (node (ref "D8") (pin "2") (pinfunction "2_2") (pintype "bidirectional"))
      (node (ref "J9") (pin "2") (pinfunction "2_2") (pintype "bidirectional"))
      (node (ref "J9") (pin "4") (pinfunction "4_4") (pintype "bidirectional"))
      (node (ref "L2") (pin "2") (pinfunction "2_2") (pintype "passive"))
      (node (ref "Q1") (pin "2") (pinfunction "S_2") (pintype "passive"))
      (node (ref "Q10") (pin "2") (pinfunction "S_2") (pintype "passive"))
      (node (ref "Q2") (pin "2") (pinfunction "S_2") (pintype "passive"))
      (node (ref "R10") (pin "1") (pinfunction "1_1") (pintype "passive"))
      (node (ref "R12") (pin "1") (pinfunction "1_1") (pintype "passive"))
      (node (ref "R13") (pin "1") (pinfunction "1_1") (pintype "passive"))
      (node (ref "R24") (pin "1") (pinfunction "1_1") (pintype "passive"))
      (node (ref "R26") (pin "7") (pinfunction "2_7") (pintype "passive"))
      (node (ref "R26") (pin "8") (pinfunction "2_8") (pintype "passive"))
      (node (ref "R34") (pin "1") (pinfunction "1_1") (pintype "passive"))
      (node (ref "R45") (pin "2") (pinfunction "2_2") (pintype "passive"))
      (node (ref "R49") (pin "2") (pinfunction "2_2") (pintype "passive"))
      (node (ref "R50") (pin "2") (pinfunction "2_2") (pintype "passive"))
      (node (ref "R51") (pin "2") (pinfunction "2_2") (pintype "passive"))
      (node (ref "R55") (pin "1") (pinfunction "1_1") (pintype "passive"))
      (node (ref "R58") (pin "2") (pinfunction "2_2") (pintype "passive"))
      (node (ref "R9") (pin "2") (pinfunction "2_2") (pintype "passive"))
      (node (ref "TF") (pin "4") (pinfunction "VDD_4") (pintype "bidirectional"))
      (node (ref "TP4") (pin "T") (pinfunction "T_T") (pintype "bidirectional"))
      (node (ref "U1") (pin "10") (pinfunction "VDD_10") (pintype "bidirectional"))
      (node (ref "U1") (pin "33") (pinfunction "VDD_33") (pintype "bidirectional"))
      (node (ref "U1") (pin "48") (pinfunction "VDD_48") (pintype "bidirectional"))
      (node (ref "U1") (pin "58") (pinfunction "VDD_58") (pintype "bidirectional"))
    )
    (net (code "140") (name "VCC_5V") (class "Default")
      (node (ref "D5") (pin "-") (pinfunction "-_-") (pintype "passive"))
      (node (ref "J9") (pin "5") (pinfunction "5_5") (pintype "bidirectional"))
    )
    (net (code "141") (name "VCC_BAT") (class "Default")
      (node (ref "BAT") (pin "1") (pinfunction "P$1_1") (pintype "bidirectional"))
      (node (ref "C26") (pin "+") (pinfunction "+_+") (pintype "passive"))
      (node (ref "L3") (pin "1") (pinfunction "1_1") (pintype "passive"))
      (node (ref "Q6") (pin "3") (pinfunction "D_3") (pintype "passive"))
      (node (ref "R20") (pin "2") (pinfunction "2_2") (pintype "passive"))
      (node (ref "U2") (pin "5") (pinfunction "BAT_5") (pintype "bidirectional"))
      (node (ref "U2") (pin "8") (pinfunction "FB_8") (pintype "input"))
    )
    (net (code "142") (name "VCC_BUCK") (class "Default")
      (node (ref "C27") (pin "2") (pinfunction "2_2") (pintype "passive"))
      (node (ref "C7") (pin "+") (pinfunction "+_+") (pintype "passive"))
      (node (ref "D6") (pin "2") (pinfunction "+_2") (pintype "passive"))
      (node (ref "D9") (pin "-") (pinfunction "-_-") (pintype "passive"))
      (node (ref "Q3") (pin "3") (pinfunction "D_3") (pintype "passive"))
      (node (ref "R43") (pin "2") (pinfunction "2_2") (pintype "passive"))
      (node (ref "TP3") (pin "T") (pinfunction "T_T") (pintype "bidirectional"))
      (node (ref "U5") (pin "1") (pinfunction "RUN_1") (pintype "bidirectional"))
      (node (ref "U5") (pin "4") (pinfunction "VIN_4") (pintype "input"))
    )
    (net (code "143") (name "VCC_SOLAR") (class "Default")
      (node (ref "C23") (pin "2") (pinfunction "2_2") (pintype "passive"))
      (node (ref "D24") (pin "2") (pinfunction "2_2") (pintype "bidirectional"))
      (node (ref "Q9") (pin "3") (pinfunction "D_3") (pintype "passive"))
      (node (ref "SOLAR") (pin "1") (pinfunction "P$1_1") (pintype "bidirectional"))
    )
    (net (code "144") (name "unconnected-(J2-ID-Pad4)") (class "Default")
      (node (ref "J2") (pin "4") (pinfunction "ID_4") (pintype "bidirectional"))
    )
    (net (code "145") (name "unconnected-(J9-Pad8)") (class "Default")
      (node (ref "J9") (pin "8") (pinfunction "8_8") (pintype "bidirectional"))
    )
    (net (code "146") (name "unconnected-(TF-CDN-Pad9)") (class "Default")
      (node (ref "TF") (pin "9") (pinfunction "CDN_9") (pintype "bidirectional"))
    )
    (net (code "147") (name "unconnected-(TF-DATA1-Pad8)") (class "Default")
      (node (ref "TF") (pin "8") (pinfunction "DATA1_8") (pintype "bidirectional"))
    )
    (net (code "148") (name "unconnected-(TF-DATA2-Pad1)") (class "Default")
      (node (ref "TF") (pin "1") (pinfunction "DATA2_1") (pintype "bidirectional"))
    )
    (net (code "149") (name "unconnected-(U1-PIO0_20-Pad11)") (class "Default")
      (node (ref "U1") (pin "11") (pinfunction "PIO0_20_11") (pintype "bidirectional"))
    )
    (net (code "150") (name "unconnected-(U1-PIO0_21-Pad22)") (class "Default")
      (node (ref "U1") (pin "22") (pinfunction "PIO0_21_22") (pintype "bidirectional"))
    )
    (net (code "151") (name "unconnected-(U1-PIO1_6-Pad64)") (class "Default")
      (node (ref "U1") (pin "64") (pinfunction "PIO1_6_64") (pintype "bidirectional"))
    )
    (net (code "152") (name "unconnected-(U1-PIO1_15-Pad57)") (class "Default")
      (node (ref "U1") (pin "57") (pinfunction "PIO1_15_57") (pintype "bidirectional"))
    )
    (net (code "153") (name "unconnected-(U3-~{INTA}-Pad3)") (class "Default")
      (node (ref "U3") (pin "3") (pinfunction "~{INTA}_3") (pintype "bidirectional"))
    )
    (net (code "154") (name "unconnected-(U4-CTS-Pad7)") (class "Default")
      (node (ref "U4") (pin "7") (pinfunction "CTS_7") (pintype "output"))
    )
    (net (code "155") (name "unconnected-(U4-DCD-Pad5)") (class "Default")
      (node (ref "U4") (pin "5") (pinfunction "DCD_5") (pintype "output"))
    )
    (net (code "156") (name "unconnected-(U4-DSR-Pad6)") (class "Default")
      (node (ref "U4") (pin "6") (pinfunction "DSR_6") (pintype "output"))
    )
    (net (code "157") (name "unconnected-(U4-DTR-Pad3)") (class "Default")
      (node (ref "U4") (pin "3") (pinfunction "DTR_3") (pintype "input"))
    )
    (net (code "158") (name "unconnected-(U4-GPIO1{slash}KBR4-Pad40)") (class "Default")
      (node (ref "U4") (pin "40") (pinfunction "GPIO1/KBR4_40") (pintype "output"))
    )
    (net (code "159") (name "unconnected-(U4-GPIO2{slash}KBR3-Pad41)") (class "Default")
      (node (ref "U4") (pin "41") (pinfunction "GPIO2/KBR3_41") (pintype "output"))
    )
    (net (code "160") (name "unconnected-(U4-GPIO3{slash}KBR2-Pad42)") (class "Default")
      (node (ref "U4") (pin "42") (pinfunction "GPIO3/KBR2_42") (pintype "output"))
    )
    (net (code "161") (name "unconnected-(U4-GPIO4{slash}KBR1-Pad43)") (class "Default")
      (node (ref "U4") (pin "43") (pinfunction "GPIO4/KBR1_43") (pintype "output"))
    )
    (net (code "162") (name "unconnected-(U4-GPIO5{slash}KBR0-Pad44)") (class "Default")
      (node (ref "U4") (pin "44") (pinfunction "GPIO5/KBR0_44") (pintype "output"))
    )
    (net (code "163") (name "unconnected-(U4-GPIO6{slash}KBC4-Pad47)") (class "Default")
      (node (ref "U4") (pin "47") (pinfunction "GPIO6/KBC4_47") (pintype "input"))
    )
    (net (code "164") (name "unconnected-(U4-GPIO7{slash}KBC3-Pad48)") (class "Default")
      (node (ref "U4") (pin "48") (pinfunction "GPIO7/KBC3_48") (pintype "bidirectional"))
    )
    (net (code "165") (name "unconnected-(U4-GPIO8{slash}KBC2-Pad49)") (class "Default")
      (node (ref "U4") (pin "49") (pinfunction "GPIO8/KBC2_49") (pintype "input"))
    )
    (net (code "166") (name "unconnected-(U4-GPIO9{slash}KBC1-Pad50)") (class "Default")
      (node (ref "U4") (pin "50") (pinfunction "GPIO9/KBC1_50") (pintype "input"))
    )
    (net (code "167") (name "unconnected-(U4-GPIO10{slash}KBC0-Pad51)") (class "Default")
      (node (ref "U4") (pin "51") (pinfunction "GPIO10/KBC0_51") (pintype "bidirectional"))
    )
    (net (code "168") (name "unconnected-(U4-LINEIN_L-Pad24)") (class "Default")
      (node (ref "U4") (pin "24") (pinfunction "LINEIN_L_24") (pintype "input"))
    )
    (net (code "169") (name "unconnected-(U4-LINEIN_R-Pad23)") (class "Default")
      (node (ref "U4") (pin "23") (pinfunction "LINEIN_R_23") (pintype "input"))
    )
    (net (code "170") (name "unconnected-(U4-NRESET-Pad16)") (class "Default")
      (node (ref "U4") (pin "16") (pinfunction "NRESET_16") (pintype "input"))
    )
    (net (code "171") (name "unconnected-(U4-PWM2-Pad36)") (class "Default")
      (node (ref "U4") (pin "36") (pinfunction "PWM2_36") (pintype "output"))
    )
    (net (code "172") (name "unconnected-(U4-RI-Pad4)") (class "Default")
      (node (ref "U4") (pin "4") (pinfunction "RI_4") (pintype "output"))
    )
    (net (code "173") (name "unconnected-(U4-RTS-Pad8)") (class "Default")
      (node (ref "U4") (pin "8") (pinfunction "RTS_8") (pintype "input"))
    )
    (net (code "174") (name "unconnected-(U4-SCL-Pad38)") (class "Default")
      (node (ref "U4") (pin "38") (pinfunction "SCL_38") (pintype "output"))
    )
    (net (code "175") (name "unconnected-(U4-SDA-Pad37)") (class "Default")
      (node (ref "U4") (pin "37") (pinfunction "SDA_37") (pintype "bidirectional"))
    )
    (net (code "176") (name "unconnected-(U4-SIM_PRESENCE-Pad34)") (class "Default")
      (node (ref "U4") (pin "34") (pinfunction "SIM_PRESENCE_34") (pintype "input"))
    )
  )
)
